# lower_pcb.net
KiCad netlist of a schematic drawn in EAGLE
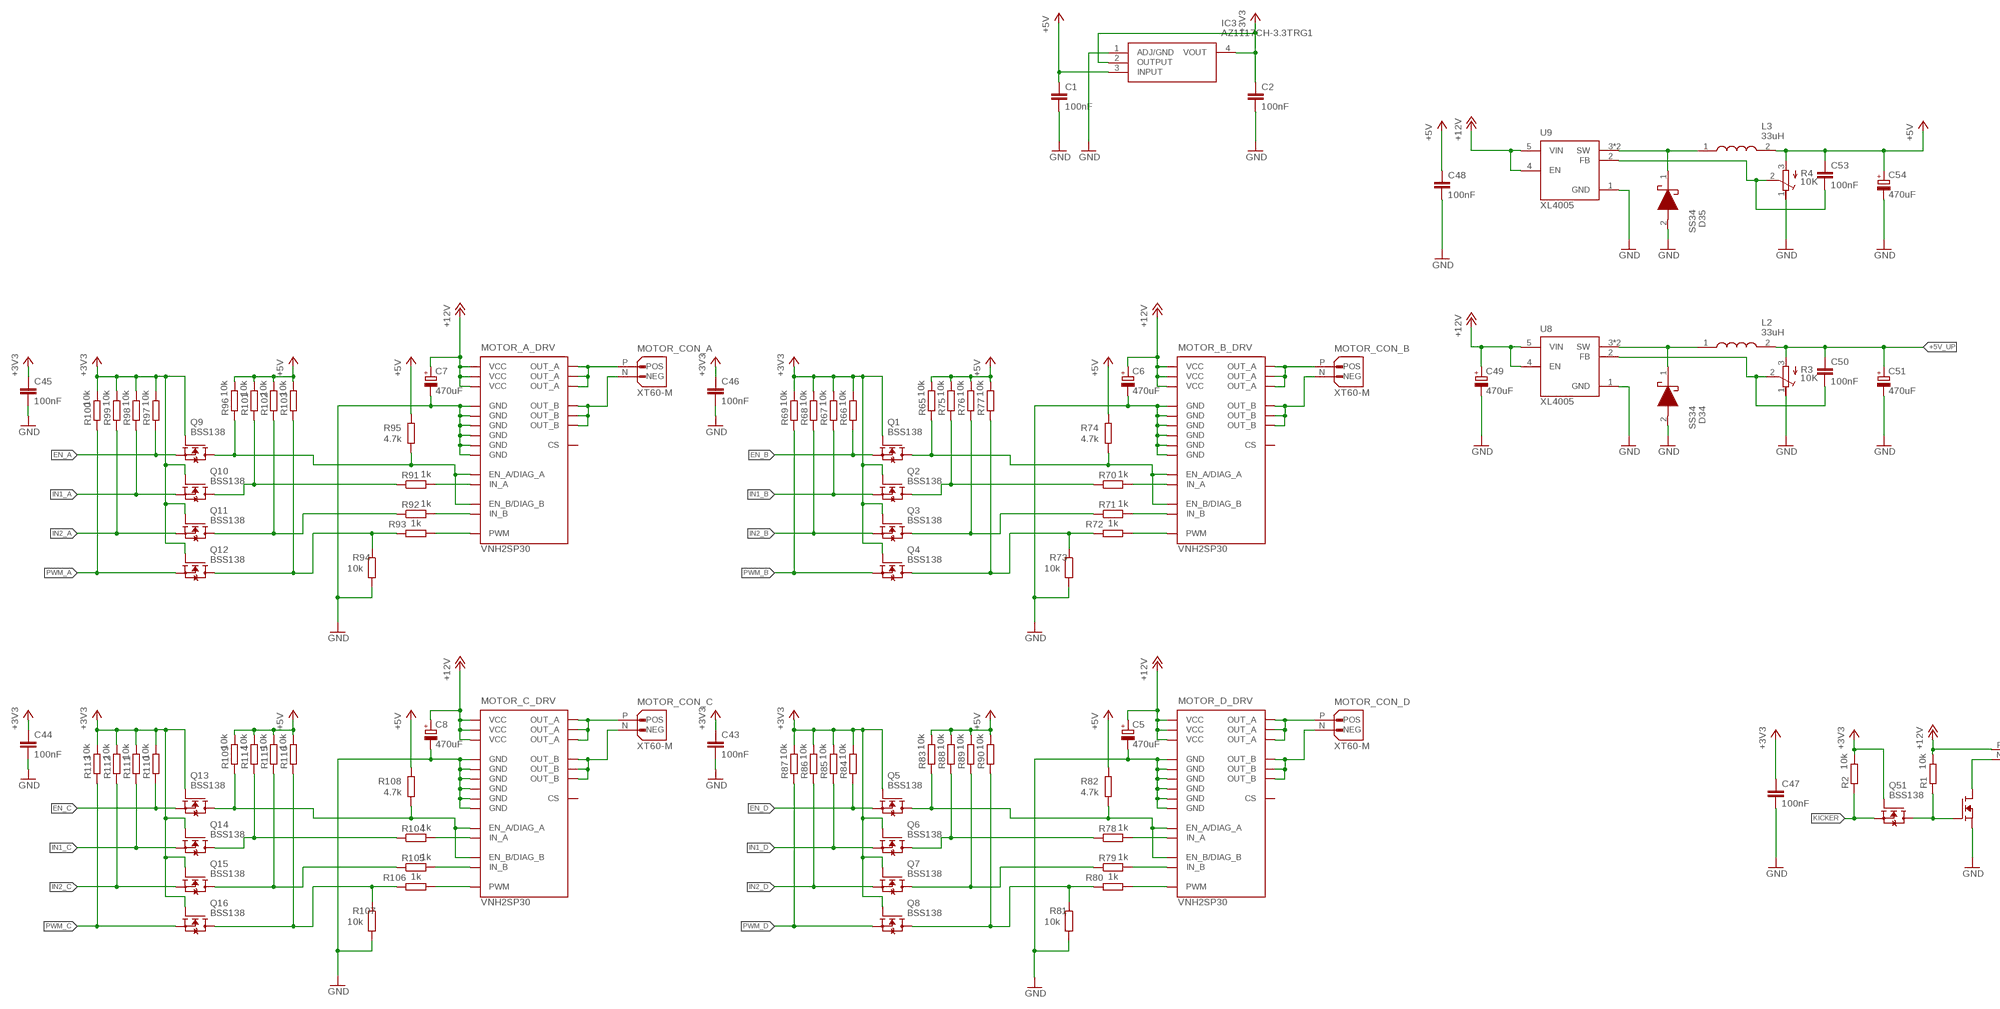
[diagram p0: schematic, sheet 1, part 1 of 2]
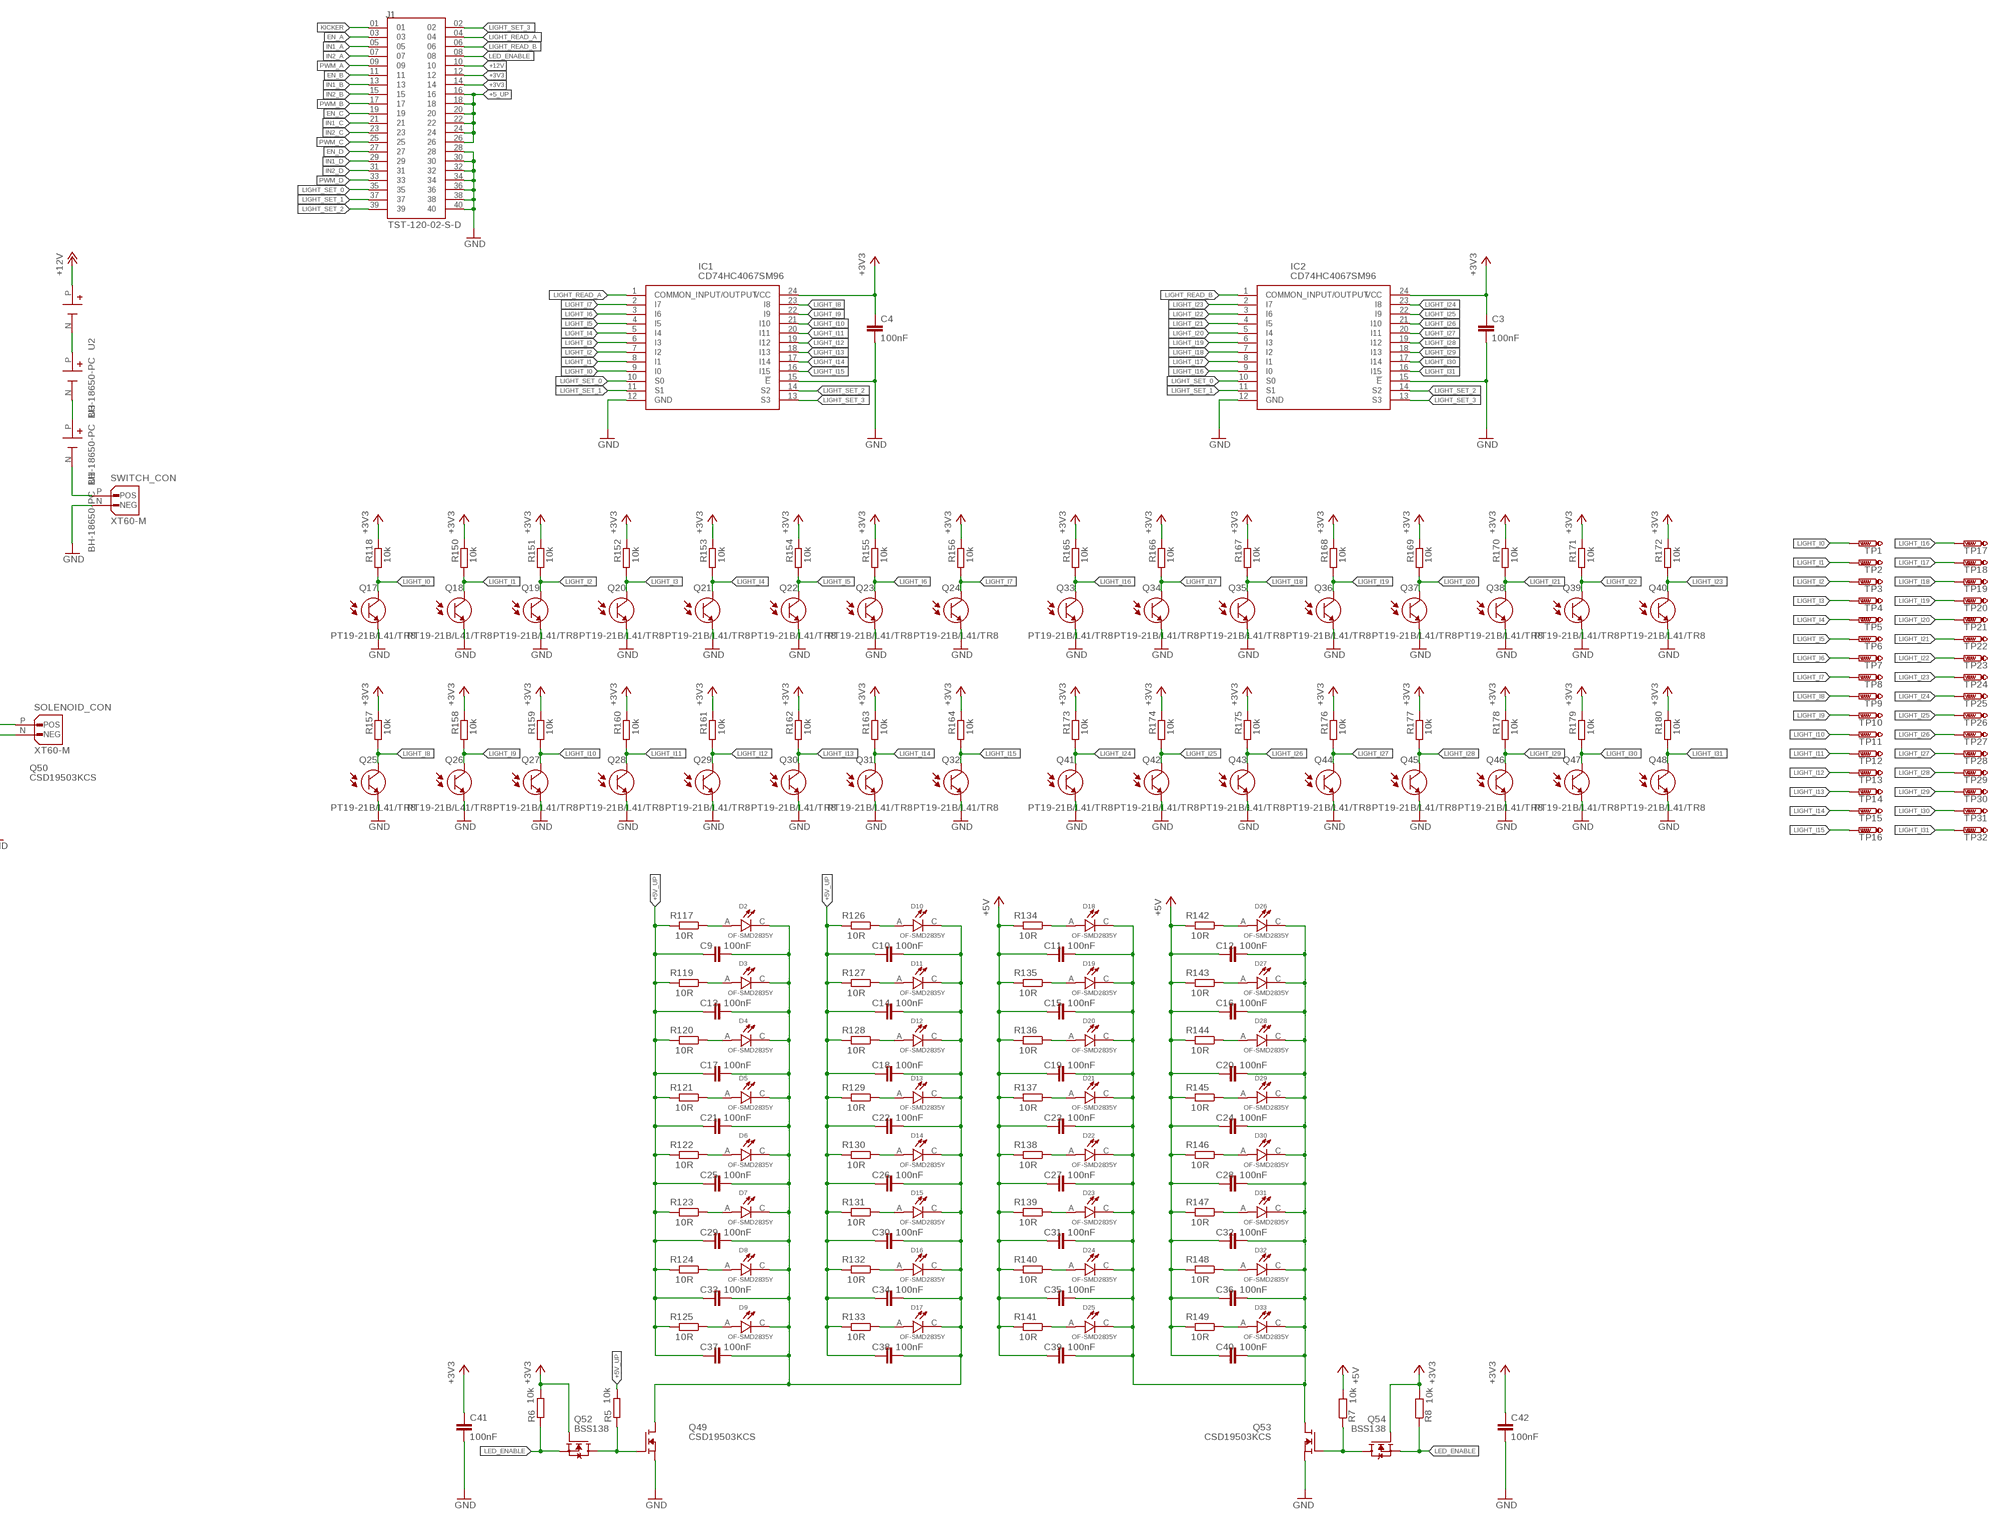
[diagram p1: schematic, sheet 1, part 2 of 2]

(export (version "E")
  (design (tool "Eeschema 10.0.6"))
  (components
    (comp (ref "C1")
      (value "100nF")
      (footprint "eagle-import:C0805")
      (libsource (lib "eagle-import") (part "C-EUC0805"))
    )
    (comp (ref "C2")
      (value "100nF")
      (footprint "eagle-import:C0805")
      (libsource (lib "eagle-import") (part "C-EUC0805"))
    )
    (comp (ref "C3")
      (value "100nF")
      (footprint "eagle-import:C0805")
      (libsource (lib "eagle-import") (part "C-EUC0805"))
    )
    (comp (ref "C4")
      (value "100nF")
      (footprint "eagle-import:C0805")
      (libsource (lib "eagle-import") (part "C-EUC0805"))
    )
    (comp (ref "C5")
      (value "470uF")
      (footprint "eagle-import:150CLZ-1010")
      (libsource (lib "eagle-import") (part "CPOL-EU150CLZ-1010"))
    )
    (comp (ref "C6")
      (value "470uF")
      (footprint "eagle-import:150CLZ-1010")
      (libsource (lib "eagle-import") (part "CPOL-EU150CLZ-1010"))
    )
    (comp (ref "C7")
      (value "470uF")
      (footprint "eagle-import:150CLZ-1010")
      (libsource (lib "eagle-import") (part "CPOL-EU150CLZ-1010"))
    )
    (comp (ref "C8")
      (value "470uF")
      (footprint "eagle-import:150CLZ-1010")
      (libsource (lib "eagle-import") (part "CPOL-EU150CLZ-1010"))
    )
    (comp (ref "C9")
      (value "100nF")
      (footprint "eagle-import:C0805")
      (libsource (lib "eagle-import") (part "C-EUC0805"))
    )
    (comp (ref "C10")
      (value "100nF")
      (footprint "eagle-import:C0805")
      (libsource (lib "eagle-import") (part "C-EUC0805"))
    )
    (comp (ref "C11")
      (value "100nF")
      (footprint "eagle-import:C0805")
      (libsource (lib "eagle-import") (part "C-EUC0805"))
    )
    (comp (ref "C12")
      (value "100nF")
      (footprint "eagle-import:C0805")
      (libsource (lib "eagle-import") (part "C-EUC0805"))
    )
    (comp (ref "C13")
      (value "100nF")
      (footprint "eagle-import:C0805")
      (libsource (lib "eagle-import") (part "C-EUC0805"))
    )
    (comp (ref "C14")
      (value "100nF")
      (footprint "eagle-import:C0805")
      (libsource (lib "eagle-import") (part "C-EUC0805"))
    )
    (comp (ref "C15")
      (value "100nF")
      (footprint "eagle-import:C0805")
      (libsource (lib "eagle-import") (part "C-EUC0805"))
    )
    (comp (ref "C16")
      (value "100nF")
      (footprint "eagle-import:C0805")
      (libsource (lib "eagle-import") (part "C-EUC0805"))
    )
    (comp (ref "C17")
      (value "100nF")
      (footprint "eagle-import:C0805")
      (libsource (lib "eagle-import") (part "C-EUC0805"))
    )
    (comp (ref "C18")
      (value "100nF")
      (footprint "eagle-import:C0805")
      (libsource (lib "eagle-import") (part "C-EUC0805"))
    )
    (comp (ref "C19")
      (value "100nF")
      (footprint "eagle-import:C0805")
      (libsource (lib "eagle-import") (part "C-EUC0805"))
    )
    (comp (ref "C20")
      (value "100nF")
      (footprint "eagle-import:C0805")
      (libsource (lib "eagle-import") (part "C-EUC0805"))
    )
    (comp (ref "C21")
      (value "100nF")
      (footprint "eagle-import:C0805")
      (libsource (lib "eagle-import") (part "C-EUC0805"))
    )
    (comp (ref "C22")
      (value "100nF")
      (footprint "eagle-import:C0805")
      (libsource (lib "eagle-import") (part "C-EUC0805"))
    )
    (comp (ref "C23")
      (value "100nF")
      (footprint "eagle-import:C0805")
      (libsource (lib "eagle-import") (part "C-EUC0805"))
    )
    (comp (ref "C24")
      (value "100nF")
      (footprint "eagle-import:C0805")
      (libsource (lib "eagle-import") (part "C-EUC0805"))
    )
    (comp (ref "C25")
      (value "100nF")
      (footprint "eagle-import:C0805")
      (libsource (lib "eagle-import") (part "C-EUC0805"))
    )
    (comp (ref "C26")
      (value "100nF")
      (footprint "eagle-import:C0805")
      (libsource (lib "eagle-import") (part "C-EUC0805"))
    )
    (comp (ref "C27")
      (value "100nF")
      (footprint "eagle-import:C0805")
      (libsource (lib "eagle-import") (part "C-EUC0805"))
    )
    (comp (ref "C28")
      (value "100nF")
      (footprint "eagle-import:C0805")
      (libsource (lib "eagle-import") (part "C-EUC0805"))
    )
    (comp (ref "C29")
      (value "100nF")
      (footprint "eagle-import:C0805")
      (libsource (lib "eagle-import") (part "C-EUC0805"))
    )
    (comp (ref "C30")
      (value "100nF")
      (footprint "eagle-import:C0805")
      (libsource (lib "eagle-import") (part "C-EUC0805"))
    )
    (comp (ref "C31")
      (value "100nF")
      (footprint "eagle-import:C0805")
      (libsource (lib "eagle-import") (part "C-EUC0805"))
    )
    (comp (ref "C32")
      (value "100nF")
      (footprint "eagle-import:C0805")
      (libsource (lib "eagle-import") (part "C-EUC0805"))
    )
    (comp (ref "C33")
      (value "100nF")
      (footprint "eagle-import:C0805")
      (libsource (lib "eagle-import") (part "C-EUC0805"))
    )
    (comp (ref "C34")
      (value "100nF")
      (footprint "eagle-import:C0805")
      (libsource (lib "eagle-import") (part "C-EUC0805"))
    )
    (comp (ref "C35")
      (value "100nF")
      (footprint "eagle-import:C0805")
      (libsource (lib "eagle-import") (part "C-EUC0805"))
    )
    (comp (ref "C36")
      (value "100nF")
      (footprint "eagle-import:C0805")
      (libsource (lib "eagle-import") (part "C-EUC0805"))
    )
    (comp (ref "C37")
      (value "100nF")
      (footprint "eagle-import:C0805")
      (libsource (lib "eagle-import") (part "C-EUC0805"))
    )
    (comp (ref "C38")
      (value "100nF")
      (footprint "eagle-import:C0805")
      (libsource (lib "eagle-import") (part "C-EUC0805"))
    )
    (comp (ref "C39")
      (value "100nF")
      (footprint "eagle-import:C0805")
      (libsource (lib "eagle-import") (part "C-EUC0805"))
    )
    (comp (ref "C40")
      (value "100nF")
      (footprint "eagle-import:C0805")
      (libsource (lib "eagle-import") (part "C-EUC0805"))
    )
    (comp (ref "C41")
      (value "100nF")
      (footprint "eagle-import:C0805")
      (libsource (lib "eagle-import") (part "C-EUC0805"))
    )
    (comp (ref "C42")
      (value "100nF")
      (footprint "eagle-import:C0805")
      (libsource (lib "eagle-import") (part "C-EUC0805"))
    )
    (comp (ref "C43")
      (value "100nF")
      (footprint "eagle-import:C0805")
      (libsource (lib "eagle-import") (part "C-EUC0805"))
    )
    (comp (ref "C44")
      (value "100nF")
      (footprint "eagle-import:C0805")
      (libsource (lib "eagle-import") (part "C-EUC0805"))
    )
    (comp (ref "C45")
      (value "100nF")
      (footprint "eagle-import:C0805")
      (libsource (lib "eagle-import") (part "C-EUC0805"))
    )
    (comp (ref "C46")
      (value "100nF")
      (footprint "eagle-import:C0805")
      (libsource (lib "eagle-import") (part "C-EUC0805"))
    )
    (comp (ref "C47")
      (value "100nF")
      (footprint "eagle-import:C0805")
      (libsource (lib "eagle-import") (part "C-EUC0805"))
    )
    (comp (ref "C48")
      (value "100nF")
      (footprint "eagle-import:C0805")
      (libsource (lib "eagle-import") (part "C-EUC0805"))
    )
    (comp (ref "C49")
      (value "470uF")
      (footprint "eagle-import:150CLZ-1010")
      (libsource (lib "eagle-import") (part "CPOL-EU150CLZ-1010"))
    )
    (comp (ref "C50")
      (value "100nF")
      (footprint "eagle-import:C0805")
      (libsource (lib "eagle-import") (part "C-EUC0805"))
    )
    (comp (ref "C51")
      (value "470uF")
      (footprint "eagle-import:150CLZ-1010")
      (libsource (lib "eagle-import") (part "CPOL-EU150CLZ-1010"))
    )
    (comp (ref "C53")
      (value "100nF")
      (footprint "eagle-import:C0805")
      (libsource (lib "eagle-import") (part "C-EUC0805"))
    )
    (comp (ref "C54")
      (value "470uF")
      (footprint "eagle-import:150CLZ-1010")
      (libsource (lib "eagle-import") (part "CPOL-EU150CLZ-1010"))
    )
    (comp (ref "D2")
      (value "OF-SMD2835Y")
      (footprint "eagle-import:LED_OF-SMD2835Y")
      (fields (field (name "MF") "Optoflash"))
      (libsource (lib "eagle-import") (part "OF-SMD2835Y"))
    )
    (comp (ref "D3")
      (value "OF-SMD2835Y")
      (footprint "eagle-import:LED_OF-SMD2835Y")
      (fields (field (name "MF") "Optoflash") (field (name "SPICEPREFIX") "D"))
      (libsource (lib "eagle-import") (part "OF-SMD2835Y"))
    )
    (comp (ref "D4")
      (value "OF-SMD2835Y")
      (footprint "eagle-import:LED_OF-SMD2835Y")
      (fields (field (name "MF") "Optoflash"))
      (libsource (lib "eagle-import") (part "OF-SMD2835Y"))
    )
    (comp (ref "D5")
      (value "OF-SMD2835Y")
      (footprint "eagle-import:LED_OF-SMD2835Y")
      (fields (field (name "MF") "Optoflash"))
      (libsource (lib "eagle-import") (part "OF-SMD2835Y"))
    )
    (comp (ref "D6")
      (value "OF-SMD2835Y")
      (footprint "eagle-import:LED_OF-SMD2835Y")
      (fields (field (name "MF") "Optoflash"))
      (libsource (lib "eagle-import") (part "OF-SMD2835Y"))
    )
    (comp (ref "D7")
      (value "OF-SMD2835Y")
      (footprint "eagle-import:LED_OF-SMD2835Y")
      (fields (field (name "MF") "Optoflash"))
      (libsource (lib "eagle-import") (part "OF-SMD2835Y"))
    )
    (comp (ref "D8")
      (value "OF-SMD2835Y")
      (footprint "eagle-import:LED_OF-SMD2835Y")
      (fields (field (name "MF") "Optoflash"))
      (libsource (lib "eagle-import") (part "OF-SMD2835Y"))
    )
    (comp (ref "D9")
      (value "OF-SMD2835Y")
      (footprint "eagle-import:LED_OF-SMD2835Y")
      (fields (field (name "MF") "Optoflash"))
      (libsource (lib "eagle-import") (part "OF-SMD2835Y"))
    )
    (comp (ref "D10")
      (value "OF-SMD2835Y")
      (footprint "eagle-import:LED_OF-SMD2835Y")
      (fields (field (name "MF") "Optoflash"))
      (libsource (lib "eagle-import") (part "OF-SMD2835Y"))
    )
    (comp (ref "D11")
      (value "OF-SMD2835Y")
      (footprint "eagle-import:LED_OF-SMD2835Y")
      (fields (field (name "MF") "Optoflash"))
      (libsource (lib "eagle-import") (part "OF-SMD2835Y"))
    )
    (comp (ref "D12")
      (value "OF-SMD2835Y")
      (footprint "eagle-import:LED_OF-SMD2835Y")
      (fields (field (name "MF") "Optoflash"))
      (libsource (lib "eagle-import") (part "OF-SMD2835Y"))
    )
    (comp (ref "D13")
      (value "OF-SMD2835Y")
      (footprint "eagle-import:LED_OF-SMD2835Y")
      (fields (field (name "MF") "Optoflash"))
      (libsource (lib "eagle-import") (part "OF-SMD2835Y"))
    )
    (comp (ref "D14")
      (value "OF-SMD2835Y")
      (footprint "eagle-import:LED_OF-SMD2835Y")
      (fields (field (name "MF") "Optoflash"))
      (libsource (lib "eagle-import") (part "OF-SMD2835Y"))
    )
    (comp (ref "D15")
      (value "OF-SMD2835Y")
      (footprint "eagle-import:LED_OF-SMD2835Y")
      (fields (field (name "MF") "Optoflash"))
      (libsource (lib "eagle-import") (part "OF-SMD2835Y"))
    )
    (comp (ref "D16")
      (value "OF-SMD2835Y")
      (footprint "eagle-import:LED_OF-SMD2835Y")
      (fields (field (name "MF") "Optoflash"))
      (libsource (lib "eagle-import") (part "OF-SMD2835Y"))
    )
    (comp (ref "D17")
      (value "OF-SMD2835Y")
      (footprint "eagle-import:LED_OF-SMD2835Y")
      (fields (field (name "MF") "Optoflash"))
      (libsource (lib "eagle-import") (part "OF-SMD2835Y"))
    )
    (comp (ref "D18")
      (value "OF-SMD2835Y")
      (footprint "eagle-import:LED_OF-SMD2835Y")
      (fields (field (name "MF") "Optoflash"))
      (libsource (lib "eagle-import") (part "OF-SMD2835Y"))
    )
    (comp (ref "D19")
      (value "OF-SMD2835Y")
      (footprint "eagle-import:LED_OF-SMD2835Y")
      (fields (field (name "MF") "Optoflash"))
      (libsource (lib "eagle-import") (part "OF-SMD2835Y"))
    )
    (comp (ref "D20")
      (value "OF-SMD2835Y")
      (footprint "eagle-import:LED_OF-SMD2835Y")
      (fields (field (name "MF") "Optoflash"))
      (libsource (lib "eagle-import") (part "OF-SMD2835Y"))
    )
    (comp (ref "D21")
      (value "OF-SMD2835Y")
      (footprint "eagle-import:LED_OF-SMD2835Y")
      (fields (field (name "MF") "Optoflash"))
      (libsource (lib "eagle-import") (part "OF-SMD2835Y"))
    )
    (comp (ref "D22")
      (value "OF-SMD2835Y")
      (footprint "eagle-import:LED_OF-SMD2835Y")
      (fields (field (name "MF") "Optoflash"))
      (libsource (lib "eagle-import") (part "OF-SMD2835Y"))
    )
    (comp (ref "D23")
      (value "OF-SMD2835Y")
      (footprint "eagle-import:LED_OF-SMD2835Y")
      (fields (field (name "MF") "Optoflash"))
      (libsource (lib "eagle-import") (part "OF-SMD2835Y"))
    )
    (comp (ref "D24")
      (value "OF-SMD2835Y")
      (footprint "eagle-import:LED_OF-SMD2835Y")
      (fields (field (name "MF") "Optoflash"))
      (libsource (lib "eagle-import") (part "OF-SMD2835Y"))
    )
    (comp (ref "D25")
      (value "OF-SMD2835Y")
      (footprint "eagle-import:LED_OF-SMD2835Y")
      (fields (field (name "MF") "Optoflash"))
      (libsource (lib "eagle-import") (part "OF-SMD2835Y"))
    )
    (comp (ref "D26")
      (value "OF-SMD2835Y")
      (footprint "eagle-import:LED_OF-SMD2835Y")
      (fields (field (name "MF") "Optoflash"))
      (libsource (lib "eagle-import") (part "OF-SMD2835Y"))
    )
    (comp (ref "D27")
      (value "OF-SMD2835Y")
      (footprint "eagle-import:LED_OF-SMD2835Y")
      (fields (field (name "MF") "Optoflash"))
      (libsource (lib "eagle-import") (part "OF-SMD2835Y"))
    )
    (comp (ref "D28")
      (value "OF-SMD2835Y")
      (footprint "eagle-import:LED_OF-SMD2835Y")
      (fields (field (name "MF") "Optoflash"))
      (libsource (lib "eagle-import") (part "OF-SMD2835Y"))
    )
    (comp (ref "D29")
      (value "OF-SMD2835Y")
      (footprint "eagle-import:LED_OF-SMD2835Y")
      (fields (field (name "MF") "Optoflash"))
      (libsource (lib "eagle-import") (part "OF-SMD2835Y"))
    )
    (comp (ref "D30")
      (value "OF-SMD2835Y")
      (footprint "eagle-import:LED_OF-SMD2835Y")
      (fields (field (name "MF") "Optoflash"))
      (libsource (lib "eagle-import") (part "OF-SMD2835Y"))
    )
    (comp (ref "D31")
      (value "OF-SMD2835Y")
      (footprint "eagle-import:LED_OF-SMD2835Y")
      (fields (field (name "MF") "Optoflash"))
      (libsource (lib "eagle-import") (part "OF-SMD2835Y"))
    )
    (comp (ref "D32")
      (value "OF-SMD2835Y")
      (footprint "eagle-import:LED_OF-SMD2835Y")
      (fields (field (name "MF") "Optoflash"))
      (libsource (lib "eagle-import") (part "OF-SMD2835Y"))
    )
    (comp (ref "D33")
      (value "OF-SMD2835Y")
      (footprint "eagle-import:LED_OF-SMD2835Y")
      (fields (field (name "MF") "Optoflash"))
      (libsource (lib "eagle-import") (part "OF-SMD2835Y"))
    )
    (comp (ref "D34")
      (value "SS34")
      (footprint "eagle-import:DIOM8059X256N")
      (fields (field (name "MOUSER_PART_NUMBER") "512-SS34"))
      (libsource (lib "eagle-import") (part "SS34"))
    )
    (comp (ref "D35")
      (value "SS34")
      (footprint "eagle-import:DIOM8059X256N")
      (fields (field (name "MOUSER_PART_NUMBER") "512-SS34"))
      (libsource (lib "eagle-import") (part "SS34"))
    )
    (comp (ref "IC1")
      (value "CD74HC4067SM96")
      (footprint "eagle-import:SOP65P780X200-24N")
      (fields (field (name "MOUSER_PART_NUMBER") "595-CD74HC4067SM96"))
      (libsource (lib "eagle-import") (part "CD74HC4067SM96"))
    )
    (comp (ref "IC2")
      (value "CD74HC4067SM96")
      (footprint "eagle-import:SOP65P780X200-24N")
      (fields (field (name "MOUSER_PART_NUMBER") "595-CD74HC4067SM96"))
      (libsource (lib "eagle-import") (part "CD74HC4067SM96"))
    )
    (comp (ref "IC3")
      (value "AZ1117CH-3.3TRG1")
      (footprint "eagle-import:SOT230P700X180-4N")
      (fields (field (name "MOUSER_PART_NUMBER") "621-AZ1117CH-3.3TRG1"))
      (libsource (lib "eagle-import") (part "AZ1117CH-3.3TRG1"))
    )
    (comp (ref "J1")
      (value "TST-120-02-S-D")
      (footprint "eagle-import:SAMTEC_TST-120-02-S-D")
      (fields (field (name "MF") "Samtec") (field (name "MP") "TST-120-02-S-D-20"))
      (libsource (lib "eagle-import") (part "TST-120-02-S-D"))
    )
    (comp (ref "L2")
      (value "33uH")
      (footprint "eagle-import:WE-HCI_1350_136523")
      (fields
        (field (name "MANUFACTURER_PART_NUMBER") "7443551151")
        (field (name "MOUSER_PART_NUMBER") "710-7443551151")
      )
      (libsource (lib "eagle-import") (part "7443551151"))
    )
    (comp (ref "L3")
      (value "33uH")
      (footprint "eagle-import:WE-HCI_1350_136523")
      (fields
        (field (name "MANUFACTURER_PART_NUMBER") "7443551151")
        (field (name "MOUSER_PART_NUMBER") "710-7443551151")
      )
      (libsource (lib "eagle-import") (part "7443551151"))
    )
    (comp (ref "MOTOR_A_DRV")
      (value "VNH2SP30")
      (footprint "eagle-import:MULTIPOWER30")
      (fields (field (name "MF") "STMicroelectronics") (field (name "SPICEPREFIX") "X"))
      (libsource (lib "eagle-import") (part "VNH2SP30"))
    )
    (comp (ref "MOTOR_B_DRV")
      (value "VNH2SP30")
      (footprint "eagle-import:MULTIPOWER30")
      (fields (field (name "MF") "STMicroelectronics") (field (name "SPICEPREFIX") "X"))
      (libsource (lib "eagle-import") (part "VNH2SP30"))
    )
    (comp (ref "MOTOR_CON_A")
      (value "XT60-M")
      (footprint "eagle-import:AMASS_XT60-M")
      (fields (field (name "MF") "AMASS"))
      (libsource (lib "eagle-import") (part "XT60-M"))
    )
    (comp (ref "MOTOR_CON_B")
      (value "XT60-M")
      (footprint "eagle-import:AMASS_XT60-M")
      (fields (field (name "MF") "AMASS"))
      (libsource (lib "eagle-import") (part "XT60-M"))
    )
    (comp (ref "MOTOR_CON_C")
      (value "XT60-M")
      (footprint "eagle-import:AMASS_XT60-M")
      (fields (field (name "MF") "AMASS"))
      (libsource (lib "eagle-import") (part "XT60-M"))
    )
    (comp (ref "MOTOR_CON_D")
      (value "XT60-M")
      (footprint "eagle-import:AMASS_XT60-M")
      (fields (field (name "MF") "AMASS"))
      (libsource (lib "eagle-import") (part "XT60-M"))
    )
    (comp (ref "MOTOR_C_DRV")
      (value "VNH2SP30")
      (footprint "eagle-import:MULTIPOWER30")
      (fields (field (name "MF") "STMicroelectronics") (field (name "SPICEPREFIX") "X"))
      (libsource (lib "eagle-import") (part "VNH2SP30"))
    )
    (comp (ref "MOTOR_D_DRV")
      (value "VNH2SP30")
      (footprint "eagle-import:MULTIPOWER30")
      (fields (field (name "MF") "STMicroelectronics") (field (name "SPICEPREFIX") "X"))
      (libsource (lib "eagle-import") (part "VNH2SP30"))
    )
    (comp (ref "Q1")
      (value "BSS138")
      (footprint "eagle-import:SOT95P240X111-3N")
      (fields (field (name "MF") "ON Semiconductor"))
      (libsource (lib "eagle-import") (part "BSS138"))
    )
    (comp (ref "Q2")
      (value "BSS138")
      (footprint "eagle-import:SOT95P240X111-3N")
      (fields (field (name "MF") "ON Semiconductor"))
      (libsource (lib "eagle-import") (part "BSS138"))
    )
    (comp (ref "Q3")
      (value "BSS138")
      (footprint "eagle-import:SOT95P240X111-3N")
      (fields (field (name "MF") "ON Semiconductor"))
      (libsource (lib "eagle-import") (part "BSS138"))
    )
    (comp (ref "Q4")
      (value "BSS138")
      (footprint "eagle-import:SOT95P240X111-3N")
      (fields (field (name "MF") "ON Semiconductor"))
      (libsource (lib "eagle-import") (part "BSS138"))
    )
    (comp (ref "Q5")
      (value "BSS138")
      (footprint "eagle-import:SOT95P240X111-3N")
      (fields (field (name "MF") "ON Semiconductor"))
      (libsource (lib "eagle-import") (part "BSS138"))
    )
    (comp (ref "Q6")
      (value "BSS138")
      (footprint "eagle-import:SOT95P240X111-3N")
      (fields (field (name "MF") "ON Semiconductor"))
      (libsource (lib "eagle-import") (part "BSS138"))
    )
    (comp (ref "Q7")
      (value "BSS138")
      (footprint "eagle-import:SOT95P240X111-3N")
      (fields (field (name "MF") "ON Semiconductor"))
      (libsource (lib "eagle-import") (part "BSS138"))
    )
    (comp (ref "Q8")
      (value "BSS138")
      (footprint "eagle-import:SOT95P240X111-3N")
      (fields (field (name "MF") "ON Semiconductor"))
      (libsource (lib "eagle-import") (part "BSS138"))
    )
    (comp (ref "Q9")
      (value "BSS138")
      (footprint "eagle-import:SOT95P240X111-3N")
      (fields (field (name "MF") "ON Semiconductor"))
      (libsource (lib "eagle-import") (part "BSS138"))
    )
    (comp (ref "Q10")
      (value "BSS138")
      (footprint "eagle-import:SOT95P240X111-3N")
      (fields (field (name "MF") "ON Semiconductor"))
      (libsource (lib "eagle-import") (part "BSS138"))
    )
    (comp (ref "Q11")
      (value "BSS138")
      (footprint "eagle-import:SOT95P240X111-3N")
      (fields (field (name "MF") "ON Semiconductor"))
      (libsource (lib "eagle-import") (part "BSS138"))
    )
    (comp (ref "Q12")
      (value "BSS138")
      (footprint "eagle-import:SOT95P240X111-3N")
      (fields (field (name "MF") "ON Semiconductor"))
      (libsource (lib "eagle-import") (part "BSS138"))
    )
    (comp (ref "Q13")
      (value "BSS138")
      (footprint "eagle-import:SOT95P240X111-3N")
      (fields (field (name "MF") "ON Semiconductor"))
      (libsource (lib "eagle-import") (part "BSS138"))
    )
    (comp (ref "Q14")
      (value "BSS138")
      (footprint "eagle-import:SOT95P240X111-3N")
      (fields (field (name "MF") "ON Semiconductor"))
      (libsource (lib "eagle-import") (part "BSS138"))
    )
    (comp (ref "Q15")
      (value "BSS138")
      (footprint "eagle-import:SOT95P240X111-3N")
      (fields (field (name "MF") "ON Semiconductor"))
      (libsource (lib "eagle-import") (part "BSS138"))
    )
    (comp (ref "Q16")
      (value "BSS138")
      (footprint "eagle-import:SOT95P240X111-3N")
      (fields (field (name "MF") "ON Semiconductor"))
      (libsource (lib "eagle-import") (part "BSS138"))
    )
    (comp (ref "Q17")
      (value "PT19-21B/L41/TR8")
      (footprint "eagle-import:XDCR_PT19-21B_L41_TR8")
      (fields (field (name "MF") "Everlight Electronics"))
      (libsource (lib "eagle-import") (part "PT19-21B/L41/TR8"))
    )
    (comp (ref "Q18")
      (value "PT19-21B/L41/TR8")
      (footprint "eagle-import:XDCR_PT19-21B_L41_TR8")
      (fields (field (name "MF") "Everlight Electronics"))
      (libsource (lib "eagle-import") (part "PT19-21B/L41/TR8"))
    )
    (comp (ref "Q19")
      (value "PT19-21B/L41/TR8")
      (footprint "eagle-import:XDCR_PT19-21B_L41_TR8")
      (fields (field (name "MF") "Everlight Electronics"))
      (libsource (lib "eagle-import") (part "PT19-21B/L41/TR8"))
    )
    (comp (ref "Q20")
      (value "PT19-21B/L41/TR8")
      (footprint "eagle-import:XDCR_PT19-21B_L41_TR8")
      (fields (field (name "MF") "Everlight Electronics"))
      (libsource (lib "eagle-import") (part "PT19-21B/L41/TR8"))
    )
    (comp (ref "Q21")
      (value "PT19-21B/L41/TR8")
      (footprint "eagle-import:XDCR_PT19-21B_L41_TR8")
      (fields (field (name "MF") "Everlight Electronics"))
      (libsource (lib "eagle-import") (part "PT19-21B/L41/TR8"))
    )
    (comp (ref "Q22")
      (value "PT19-21B/L41/TR8")
      (footprint "eagle-import:XDCR_PT19-21B_L41_TR8")
      (fields (field (name "MF") "Everlight Electronics"))
      (libsource (lib "eagle-import") (part "PT19-21B/L41/TR8"))
    )
    (comp (ref "Q23")
      (value "PT19-21B/L41/TR8")
      (footprint "eagle-import:XDCR_PT19-21B_L41_TR8")
      (fields (field (name "MF") "Everlight Electronics"))
      (libsource (lib "eagle-import") (part "PT19-21B/L41/TR8"))
    )
    (comp (ref "Q24")
      (value "PT19-21B/L41/TR8")
      (footprint "eagle-import:XDCR_PT19-21B_L41_TR8")
      (fields (field (name "MF") "Everlight Electronics"))
      (libsource (lib "eagle-import") (part "PT19-21B/L41/TR8"))
    )
    (comp (ref "Q25")
      (value "PT19-21B/L41/TR8")
      (footprint "eagle-import:XDCR_PT19-21B_L41_TR8")
      (fields (field (name "MF") "Everlight Electronics"))
      (libsource (lib "eagle-import") (part "PT19-21B/L41/TR8"))
    )
    (comp (ref "Q26")
      (value "PT19-21B/L41/TR8")
      (footprint "eagle-import:XDCR_PT19-21B_L41_TR8")
      (fields (field (name "MF") "Everlight Electronics"))
      (libsource (lib "eagle-import") (part "PT19-21B/L41/TR8"))
    )
    (comp (ref "Q27")
      (value "PT19-21B/L41/TR8")
      (footprint "eagle-import:XDCR_PT19-21B_L41_TR8")
      (fields (field (name "MF") "Everlight Electronics"))
      (libsource (lib "eagle-import") (part "PT19-21B/L41/TR8"))
    )
    (comp (ref "Q28")
      (value "PT19-21B/L41/TR8")
      (footprint "eagle-import:XDCR_PT19-21B_L41_TR8")
      (fields (field (name "MF") "Everlight Electronics"))
      (libsource (lib "eagle-import") (part "PT19-21B/L41/TR8"))
    )
    (comp (ref "Q29")
      (value "PT19-21B/L41/TR8")
      (footprint "eagle-import:XDCR_PT19-21B_L41_TR8")
      (fields (field (name "MF") "Everlight Electronics"))
      (libsource (lib "eagle-import") (part "PT19-21B/L41/TR8"))
    )
    (comp (ref "Q30")
      (value "PT19-21B/L41/TR8")
      (footprint "eagle-import:XDCR_PT19-21B_L41_TR8")
      (fields (field (name "MF") "Everlight Electronics"))
      (libsource (lib "eagle-import") (part "PT19-21B/L41/TR8"))
    )
    (comp (ref "Q31")
      (value "PT19-21B/L41/TR8")
      (footprint "eagle-import:XDCR_PT19-21B_L41_TR8")
      (fields (field (name "MF") "Everlight Electronics"))
      (libsource (lib "eagle-import") (part "PT19-21B/L41/TR8"))
    )
    (comp (ref "Q32")
      (value "PT19-21B/L41/TR8")
      (footprint "eagle-import:XDCR_PT19-21B_L41_TR8")
      (fields (field (name "MF") "Everlight Electronics"))
      (libsource (lib "eagle-import") (part "PT19-21B/L41/TR8"))
    )
    (comp (ref "Q33")
      (value "PT19-21B/L41/TR8")
      (footprint "eagle-import:XDCR_PT19-21B_L41_TR8")
      (fields (field (name "MF") "Everlight Electronics"))
      (libsource (lib "eagle-import") (part "PT19-21B/L41/TR8"))
    )
    (comp (ref "Q34")
      (value "PT19-21B/L41/TR8")
      (footprint "eagle-import:XDCR_PT19-21B_L41_TR8")
      (fields (field (name "MF") "Everlight Electronics"))
      (libsource (lib "eagle-import") (part "PT19-21B/L41/TR8"))
    )
    (comp (ref "Q35")
      (value "PT19-21B/L41/TR8")
      (footprint "eagle-import:XDCR_PT19-21B_L41_TR8")
      (fields (field (name "MF") "Everlight Electronics"))
      (libsource (lib "eagle-import") (part "PT19-21B/L41/TR8"))
    )
    (comp (ref "Q36")
      (value "PT19-21B/L41/TR8")
      (footprint "eagle-import:XDCR_PT19-21B_L41_TR8")
      (fields (field (name "MF") "Everlight Electronics"))
      (libsource (lib "eagle-import") (part "PT19-21B/L41/TR8"))
    )
    (comp (ref "Q37")
      (value "PT19-21B/L41/TR8")
      (footprint "eagle-import:XDCR_PT19-21B_L41_TR8")
      (fields (field (name "MF") "Everlight Electronics"))
      (libsource (lib "eagle-import") (part "PT19-21B/L41/TR8"))
    )
    (comp (ref "Q38")
      (value "PT19-21B/L41/TR8")
      (footprint "eagle-import:XDCR_PT19-21B_L41_TR8")
      (fields (field (name "MF") "Everlight Electronics"))
      (libsource (lib "eagle-import") (part "PT19-21B/L41/TR8"))
    )
    (comp (ref "Q39")
      (value "PT19-21B/L41/TR8")
      (footprint "eagle-import:XDCR_PT19-21B_L41_TR8")
      (fields (field (name "MF") "Everlight Electronics"))
      (libsource (lib "eagle-import") (part "PT19-21B/L41/TR8"))
    )
    (comp (ref "Q40")
      (value "PT19-21B/L41/TR8")
      (footprint "eagle-import:XDCR_PT19-21B_L41_TR8")
      (fields (field (name "MF") "Everlight Electronics"))
      (libsource (lib "eagle-import") (part "PT19-21B/L41/TR8"))
    )
    (comp (ref "Q41")
      (value "PT19-21B/L41/TR8")
      (footprint "eagle-import:XDCR_PT19-21B_L41_TR8")
      (fields (field (name "MF") "Everlight Electronics"))
      (libsource (lib "eagle-import") (part "PT19-21B/L41/TR8"))
    )
    (comp (ref "Q42")
      (value "PT19-21B/L41/TR8")
      (footprint "eagle-import:XDCR_PT19-21B_L41_TR8")
      (fields (field (name "MF") "Everlight Electronics"))
      (libsource (lib "eagle-import") (part "PT19-21B/L41/TR8"))
    )
    (comp (ref "Q43")
      (value "PT19-21B/L41/TR8")
      (footprint "eagle-import:XDCR_PT19-21B_L41_TR8")
      (fields (field (name "MF") "Everlight Electronics"))
      (libsource (lib "eagle-import") (part "PT19-21B/L41/TR8"))
    )
    (comp (ref "Q44")
      (value "PT19-21B/L41/TR8")
      (footprint "eagle-import:XDCR_PT19-21B_L41_TR8")
      (fields (field (name "MF") "Everlight Electronics"))
      (libsource (lib "eagle-import") (part "PT19-21B/L41/TR8"))
    )
    (comp (ref "Q45")
      (value "PT19-21B/L41/TR8")
      (footprint "eagle-import:XDCR_PT19-21B_L41_TR8")
      (fields (field (name "MF") "Everlight Electronics"))
      (libsource (lib "eagle-import") (part "PT19-21B/L41/TR8"))
    )
    (comp (ref "Q46")
      (value "PT19-21B/L41/TR8")
      (footprint "eagle-import:XDCR_PT19-21B_L41_TR8")
      (fields (field (name "MF") "Everlight Electronics"))
      (libsource (lib "eagle-import") (part "PT19-21B/L41/TR8"))
    )
    (comp (ref "Q47")
      (value "PT19-21B/L41/TR8")
      (footprint "eagle-import:XDCR_PT19-21B_L41_TR8")
      (fields (field (name "MF") "Everlight Electronics"))
      (libsource (lib "eagle-import") (part "PT19-21B/L41/TR8"))
    )
    (comp (ref "Q48")
      (value "PT19-21B/L41/TR8")
      (footprint "eagle-import:XDCR_PT19-21B_L41_TR8")
      (fields (field (name "MF") "Everlight Electronics"))
      (libsource (lib "eagle-import") (part "PT19-21B/L41/TR8"))
    )
    (comp (ref "Q49")
      (value "CSD19503KCS")
      (footprint "eagle-import:TO254P1036X470X1965-3")
      (fields (field (name "MF") "Texas Instruments"))
      (libsource (lib "eagle-import") (part "CSD19503KCS"))
    )
    (comp (ref "Q50")
      (value "CSD19503KCS")
      (footprint "eagle-import:TO254P1036X470X1965-3")
      (fields (field (name "MF") "Texas Instruments"))
      (libsource (lib "eagle-import") (part "CSD19503KCS"))
    )
    (comp (ref "Q51")
      (value "BSS138")
      (footprint "eagle-import:SOT95P240X111-3N")
      (fields (field (name "MF") "ON Semiconductor"))
      (libsource (lib "eagle-import") (part "BSS138"))
    )
    (comp (ref "Q52")
      (value "BSS138")
      (footprint "eagle-import:SOT95P240X111-3N")
      (fields (field (name "MF") "ON Semiconductor"))
      (libsource (lib "eagle-import") (part "BSS138"))
    )
    (comp (ref "Q53")
      (value "CSD19503KCS")
      (footprint "eagle-import:TO254P1036X470X1965-3")
      (fields (field (name "MF") "Texas Instruments"))
      (libsource (lib "eagle-import") (part "CSD19503KCS"))
    )
    (comp (ref "Q54")
      (value "BSS138")
      (footprint "eagle-import:SOT95P240X111-3N")
      (fields (field (name "MF") "ON Semiconductor"))
      (libsource (lib "eagle-import") (part "BSS138"))
    )
    (comp (ref "R1")
      (value "10k")
      (footprint "eagle-import:R1206")
      (libsource (lib "eagle-import") (part "R-EU_R1206"))
    )
    (comp (ref "R2")
      (value "10k")
      (footprint "eagle-import:R1206")
      (libsource (lib "eagle-import") (part "R-EU_R1206"))
    )
    (comp (ref "R3")
      (value "10K")
      (footprint "eagle-import:RTRIM3314J")
      (libsource (lib "eagle-import") (part "R-TRIMM3314J"))
    )
    (comp (ref "R4")
      (value "10K")
      (footprint "eagle-import:RTRIM3314J")
      (libsource (lib "eagle-import") (part "R-TRIMM3314J"))
    )
    (comp (ref "R5")
      (value "10k")
      (footprint "eagle-import:R1206")
      (libsource (lib "eagle-import") (part "R-EU_R1206"))
    )
    (comp (ref "R6")
      (value "10k")
      (footprint "eagle-import:R1206")
      (libsource (lib "eagle-import") (part "R-EU_R1206"))
    )
    (comp (ref "R7")
      (value "10k")
      (footprint "eagle-import:R1206")
      (libsource (lib "eagle-import") (part "R-EU_R1206"))
    )
    (comp (ref "R8")
      (value "10k")
      (footprint "eagle-import:R1206")
      (libsource (lib "eagle-import") (part "R-EU_R1206"))
    )
    (comp (ref "R65")
      (value "10k")
      (footprint "eagle-import:R1206")
      (libsource (lib "eagle-import") (part "R-EU_R1206"))
    )
    (comp (ref "R66")
      (value "10k")
      (footprint "eagle-import:R1206")
      (libsource (lib "eagle-import") (part "R-EU_R1206"))
    )
    (comp (ref "R67")
      (value "10k")
      (footprint "eagle-import:R1206")
      (libsource (lib "eagle-import") (part "R-EU_R1206"))
    )
    (comp (ref "R68")
      (value "10k")
      (footprint "eagle-import:R1206")
      (libsource (lib "eagle-import") (part "R-EU_R1206"))
    )
    (comp (ref "R69")
      (value "10k")
      (footprint "eagle-import:R1206")
      (libsource (lib "eagle-import") (part "R-EU_R1206"))
    )
    (comp (ref "R70")
      (value "1k")
      (footprint "eagle-import:R1206")
      (libsource (lib "eagle-import") (part "R-EU_R1206"))
    )
    (comp (ref "R71")
      (value "1k")
      (footprint "eagle-import:R1206")
      (libsource (lib "eagle-import") (part "R-EU_R1206"))
    )
    (comp (ref "R72")
      (value "1k")
      (footprint "eagle-import:R1206")
      (libsource (lib "eagle-import") (part "R-EU_R1206"))
    )
    (comp (ref "R73")
      (value "10k")
      (footprint "eagle-import:R1206")
      (libsource (lib "eagle-import") (part "R-EU_R1206"))
    )
    (comp (ref "R74")
      (value "4.7k")
      (footprint "eagle-import:R1206")
      (libsource (lib "eagle-import") (part "R-EU_R1206"))
    )
    (comp (ref "R75")
      (value "10k")
      (footprint "eagle-import:R1206")
      (libsource (lib "eagle-import") (part "R-EU_R1206"))
    )
    (comp (ref "R76")
      (value "10k")
      (footprint "eagle-import:R1206")
      (libsource (lib "eagle-import") (part "R-EU_R1206"))
    )
    (comp (ref "R77")
      (value "10k")
      (footprint "eagle-import:R1206")
      (libsource (lib "eagle-import") (part "R-EU_R1206"))
    )
    (comp (ref "R78")
      (value "1k")
      (footprint "eagle-import:R1206")
      (libsource (lib "eagle-import") (part "R-EU_R1206"))
    )
    (comp (ref "R79")
      (value "1k")
      (footprint "eagle-import:R1206")
      (libsource (lib "eagle-import") (part "R-EU_R1206"))
    )
    (comp (ref "R80")
      (value "1k")
      (footprint "eagle-import:R1206")
      (libsource (lib "eagle-import") (part "R-EU_R1206"))
    )
    (comp (ref "R81")
      (value "10k")
      (footprint "eagle-import:R1206")
      (libsource (lib "eagle-import") (part "R-EU_R1206"))
    )
    (comp (ref "R82")
      (value "4.7k")
      (footprint "eagle-import:R1206")
      (libsource (lib "eagle-import") (part "R-EU_R1206"))
    )
    (comp (ref "R83")
      (value "10k")
      (footprint "eagle-import:R1206")
      (libsource (lib "eagle-import") (part "R-EU_R1206"))
    )
    (comp (ref "R84")
      (value "10k")
      (footprint "eagle-import:R1206")
      (libsource (lib "eagle-import") (part "R-EU_R1206"))
    )
    (comp (ref "R85")
      (value "10k")
      (footprint "eagle-import:R1206")
      (libsource (lib "eagle-import") (part "R-EU_R1206"))
    )
    (comp (ref "R86")
      (value "10k")
      (footprint "eagle-import:R1206")
      (libsource (lib "eagle-import") (part "R-EU_R1206"))
    )
    (comp (ref "R87")
      (value "10k")
      (footprint "eagle-import:R1206")
      (libsource (lib "eagle-import") (part "R-EU_R1206"))
    )
    (comp (ref "R88")
      (value "10k")
      (footprint "eagle-import:R1206")
      (libsource (lib "eagle-import") (part "R-EU_R1206"))
    )
    (comp (ref "R89")
      (value "10k")
      (footprint "eagle-import:R1206")
      (libsource (lib "eagle-import") (part "R-EU_R1206"))
    )
    (comp (ref "R90")
      (value "10k")
      (footprint "eagle-import:R1206")
      (libsource (lib "eagle-import") (part "R-EU_R1206"))
    )
    (comp (ref "R91")
      (value "1k")
      (footprint "eagle-import:R1206")
      (libsource (lib "eagle-import") (part "R-EU_R1206"))
    )
    (comp (ref "R92")
      (value "1k")
      (footprint "eagle-import:R1206")
      (libsource (lib "eagle-import") (part "R-EU_R1206"))
    )
    (comp (ref "R93")
      (value "1k")
      (footprint "eagle-import:R1206")
      (libsource (lib "eagle-import") (part "R-EU_R1206"))
    )
    (comp (ref "R94")
      (value "10k")
      (footprint "eagle-import:R1206")
      (libsource (lib "eagle-import") (part "R-EU_R1206"))
    )
    (comp (ref "R95")
      (value "4.7k")
      (footprint "eagle-import:R1206")
      (libsource (lib "eagle-import") (part "R-EU_R1206"))
    )
    (comp (ref "R96")
      (value "10k")
      (footprint "eagle-import:R1206")
      (libsource (lib "eagle-import") (part "R-EU_R1206"))
    )
    (comp (ref "R97")
      (value "10k")
      (footprint "eagle-import:R1206")
      (libsource (lib "eagle-import") (part "R-EU_R1206"))
    )
    (comp (ref "R98")
      (value "10k")
      (footprint "eagle-import:R1206")
      (libsource (lib "eagle-import") (part "R-EU_R1206"))
    )
    (comp (ref "R99")
      (value "10k")
      (footprint "eagle-import:R1206")
      (libsource (lib "eagle-import") (part "R-EU_R1206"))
    )
    (comp (ref "R100")
      (value "10k")
      (footprint "eagle-import:R1206")
      (libsource (lib "eagle-import") (part "R-EU_R1206"))
    )
    (comp (ref "R101")
      (value "10k")
      (footprint "eagle-import:R1206")
      (libsource (lib "eagle-import") (part "R-EU_R1206"))
    )
    (comp (ref "R102")
      (value "10k")
      (footprint "eagle-import:R1206")
      (libsource (lib "eagle-import") (part "R-EU_R1206"))
    )
    (comp (ref "R103")
      (value "10k")
      (footprint "eagle-import:R1206")
      (libsource (lib "eagle-import") (part "R-EU_R1206"))
    )
    (comp (ref "R104")
      (value "1k")
      (footprint "eagle-import:R1206")
      (libsource (lib "eagle-import") (part "R-EU_R1206"))
    )
    (comp (ref "R105")
      (value "1k")
      (footprint "eagle-import:R1206")
      (libsource (lib "eagle-import") (part "R-EU_R1206"))
    )
    (comp (ref "R106")
      (value "1k")
      (footprint "eagle-import:R1206")
      (libsource (lib "eagle-import") (part "R-EU_R1206"))
    )
    (comp (ref "R107")
      (value "10k")
      (footprint "eagle-import:R1206")
      (libsource (lib "eagle-import") (part "R-EU_R1206"))
    )
    (comp (ref "R108")
      (value "4.7k")
      (footprint "eagle-import:R1206")
      (libsource (lib "eagle-import") (part "R-EU_R1206"))
    )
    (comp (ref "R109")
      (value "10k")
      (footprint "eagle-import:R1206")
      (libsource (lib "eagle-import") (part "R-EU_R1206"))
    )
    (comp (ref "R110")
      (value "10k")
      (footprint "eagle-import:R1206")
      (libsource (lib "eagle-import") (part "R-EU_R1206"))
    )
    (comp (ref "R111")
      (value "10k")
      (footprint "eagle-import:R1206")
      (libsource (lib "eagle-import") (part "R-EU_R1206"))
    )
    (comp (ref "R112")
      (value "10k")
      (footprint "eagle-import:R1206")
      (libsource (lib "eagle-import") (part "R-EU_R1206"))
    )
    (comp (ref "R113")
      (value "10k")
      (footprint "eagle-import:R1206")
      (libsource (lib "eagle-import") (part "R-EU_R1206"))
    )
    (comp (ref "R114")
      (value "10k")
      (footprint "eagle-import:R1206")
      (libsource (lib "eagle-import") (part "R-EU_R1206"))
    )
    (comp (ref "R115")
      (value "10k")
      (footprint "eagle-import:R1206")
      (libsource (lib "eagle-import") (part "R-EU_R1206"))
    )
    (comp (ref "R116")
      (value "10k")
      (footprint "eagle-import:R1206")
      (libsource (lib "eagle-import") (part "R-EU_R1206"))
    )
    (comp (ref "R117")
      (value "10R")
      (footprint "eagle-import:R1206")
      (libsource (lib "eagle-import") (part "R-EU_R1206"))
    )
    (comp (ref "R118")
      (value "10k")
      (footprint "eagle-import:R1206")
      (libsource (lib "eagle-import") (part "R-EU_R1206"))
    )
    (comp (ref "R119")
      (value "10R")
      (footprint "eagle-import:R1206")
      (libsource (lib "eagle-import") (part "R-EU_R1206"))
    )
    (comp (ref "R120")
      (value "10R")
      (footprint "eagle-import:R1206")
      (libsource (lib "eagle-import") (part "R-EU_R1206"))
    )
    (comp (ref "R121")
      (value "10R")
      (footprint "eagle-import:R1206")
      (libsource (lib "eagle-import") (part "R-EU_R1206"))
    )
    (comp (ref "R122")
      (value "10R")
      (footprint "eagle-import:R1206")
      (libsource (lib "eagle-import") (part "R-EU_R1206"))
    )
    (comp (ref "R123")
      (value "10R")
      (footprint "eagle-import:R1206")
      (libsource (lib "eagle-import") (part "R-EU_R1206"))
    )
    (comp (ref "R124")
      (value "10R")
      (footprint "eagle-import:R1206")
      (libsource (lib "eagle-import") (part "R-EU_R1206"))
    )
    (comp (ref "R125")
      (value "10R")
      (footprint "eagle-import:R1206")
      (libsource (lib "eagle-import") (part "R-EU_R1206"))
    )
    (comp (ref "R126")
      (value "10R")
      (footprint "eagle-import:R1206")
      (libsource (lib "eagle-import") (part "R-EU_R1206"))
    )
    (comp (ref "R127")
      (value "10R")
      (footprint "eagle-import:R1206")
      (libsource (lib "eagle-import") (part "R-EU_R1206"))
    )
    (comp (ref "R128")
      (value "10R")
      (footprint "eagle-import:R1206")
      (libsource (lib "eagle-import") (part "R-EU_R1206"))
    )
    (comp (ref "R129")
      (value "10R")
      (footprint "eagle-import:R1206")
      (libsource (lib "eagle-import") (part "R-EU_R1206"))
    )
    (comp (ref "R130")
      (value "10R")
      (footprint "eagle-import:R1206")
      (libsource (lib "eagle-import") (part "R-EU_R1206"))
    )
    (comp (ref "R131")
      (value "10R")
      (footprint "eagle-import:R1206")
      (libsource (lib "eagle-import") (part "R-EU_R1206"))
    )
    (comp (ref "R132")
      (value "10R")
      (footprint "eagle-import:R1206")
      (libsource (lib "eagle-import") (part "R-EU_R1206"))
    )
    (comp (ref "R133")
      (value "10R")
      (footprint "eagle-import:R1206")
      (libsource (lib "eagle-import") (part "R-EU_R1206"))
    )
    (comp (ref "R134")
      (value "10R")
      (footprint "eagle-import:R1206")
      (libsource (lib "eagle-import") (part "R-EU_R1206"))
    )
    (comp (ref "R135")
      (value "10R")
      (footprint "eagle-import:R1206")
      (libsource (lib "eagle-import") (part "R-EU_R1206"))
    )
    (comp (ref "R136")
      (value "10R")
      (footprint "eagle-import:R1206")
      (libsource (lib "eagle-import") (part "R-EU_R1206"))
    )
    (comp (ref "R137")
      (value "10R")
      (footprint "eagle-import:R1206")
      (libsource (lib "eagle-import") (part "R-EU_R1206"))
    )
    (comp (ref "R138")
      (value "10R")
      (footprint "eagle-import:R1206")
      (libsource (lib "eagle-import") (part "R-EU_R1206"))
    )
    (comp (ref "R139")
      (value "10R")
      (footprint "eagle-import:R1206")
      (libsource (lib "eagle-import") (part "R-EU_R1206"))
    )
    (comp (ref "R140")
      (value "10R")
      (footprint "eagle-import:R1206")
      (libsource (lib "eagle-import") (part "R-EU_R1206"))
    )
    (comp (ref "R141")
      (value "10R")
      (footprint "eagle-import:R1206")
      (libsource (lib "eagle-import") (part "R-EU_R1206"))
    )
    (comp (ref "R142")
      (value "10R")
      (footprint "eagle-import:R1206")
      (libsource (lib "eagle-import") (part "R-EU_R1206"))
    )
    (comp (ref "R143")
      (value "10R")
      (footprint "eagle-import:R1206")
      (libsource (lib "eagle-import") (part "R-EU_R1206"))
    )
    (comp (ref "R144")
      (value "10R")
      (footprint "eagle-import:R1206")
      (libsource (lib "eagle-import") (part "R-EU_R1206"))
    )
    (comp (ref "R145")
      (value "10R")
      (footprint "eagle-import:R1206")
      (libsource (lib "eagle-import") (part "R-EU_R1206"))
    )
    (comp (ref "R146")
      (value "10R")
      (footprint "eagle-import:R1206")
      (libsource (lib "eagle-import") (part "R-EU_R1206"))
    )
    (comp (ref "R147")
      (value "10R")
      (footprint "eagle-import:R1206")
      (libsource (lib "eagle-import") (part "R-EU_R1206"))
    )
    (comp (ref "R148")
      (value "10R")
      (footprint "eagle-import:R1206")
      (libsource (lib "eagle-import") (part "R-EU_R1206"))
    )
    (comp (ref "R149")
      (value "10R")
      (footprint "eagle-import:R1206")
      (libsource (lib "eagle-import") (part "R-EU_R1206"))
    )
    (comp (ref "R150")
      (value "10k")
      (footprint "eagle-import:R1206")
      (libsource (lib "eagle-import") (part "R-EU_R1206"))
    )
    (comp (ref "R151")
      (value "10k")
      (footprint "eagle-import:R1206")
      (libsource (lib "eagle-import") (part "R-EU_R1206"))
    )
    (comp (ref "R152")
      (value "10k")
      (footprint "eagle-import:R1206")
      (libsource (lib "eagle-import") (part "R-EU_R1206"))
    )
    (comp (ref "R153")
      (value "10k")
      (footprint "eagle-import:R1206")
      (libsource (lib "eagle-import") (part "R-EU_R1206"))
    )
    (comp (ref "R154")
      (value "10k")
      (footprint "eagle-import:R1206")
      (libsource (lib "eagle-import") (part "R-EU_R1206"))
    )
    (comp (ref "R155")
      (value "10k")
      (footprint "eagle-import:R1206")
      (libsource (lib "eagle-import") (part "R-EU_R1206"))
    )
    (comp (ref "R156")
      (value "10k")
      (footprint "eagle-import:R1206")
      (libsource (lib "eagle-import") (part "R-EU_R1206"))
    )
    (comp (ref "R157")
      (value "10k")
      (footprint "eagle-import:R1206")
      (libsource (lib "eagle-import") (part "R-EU_R1206"))
    )
    (comp (ref "R158")
      (value "10k")
      (footprint "eagle-import:R1206")
      (libsource (lib "eagle-import") (part "R-EU_R1206"))
    )
    (comp (ref "R159")
      (value "10k")
      (footprint "eagle-import:R1206")
      (libsource (lib "eagle-import") (part "R-EU_R1206"))
    )
    (comp (ref "R160")
      (value "10k")
      (footprint "eagle-import:R1206")
      (libsource (lib "eagle-import") (part "R-EU_R1206"))
    )
    (comp (ref "R161")
      (value "10k")
      (footprint "eagle-import:R1206")
      (libsource (lib "eagle-import") (part "R-EU_R1206"))
    )
    (comp (ref "R162")
      (value "10k")
      (footprint "eagle-import:R1206")
      (libsource (lib "eagle-import") (part "R-EU_R1206"))
    )
    (comp (ref "R163")
      (value "10k")
      (footprint "eagle-import:R1206")
      (libsource (lib "eagle-import") (part "R-EU_R1206"))
    )
    (comp (ref "R164")
      (value "10k")
      (footprint "eagle-import:R1206")
      (libsource (lib "eagle-import") (part "R-EU_R1206"))
    )
    (comp (ref "R165")
      (value "10k")
      (footprint "eagle-import:R1206")
      (libsource (lib "eagle-import") (part "R-EU_R1206"))
    )
    (comp (ref "R166")
      (value "10k")
      (footprint "eagle-import:R1206")
      (libsource (lib "eagle-import") (part "R-EU_R1206"))
    )
    (comp (ref "R167")
      (value "10k")
      (footprint "eagle-import:R1206")
      (libsource (lib "eagle-import") (part "R-EU_R1206"))
    )
    (comp (ref "R168")
      (value "10k")
      (footprint "eagle-import:R1206")
      (libsource (lib "eagle-import") (part "R-EU_R1206"))
    )
    (comp (ref "R169")
      (value "10k")
      (footprint "eagle-import:R1206")
      (libsource (lib "eagle-import") (part "R-EU_R1206"))
    )
    (comp (ref "R170")
      (value "10k")
      (footprint "eagle-import:R1206")
      (libsource (lib "eagle-import") (part "R-EU_R1206"))
    )
    (comp (ref "R171")
      (value "10k")
      (footprint "eagle-import:R1206")
      (libsource (lib "eagle-import") (part "R-EU_R1206"))
    )
    (comp (ref "R172")
      (value "10k")
      (footprint "eagle-import:R1206")
      (libsource (lib "eagle-import") (part "R-EU_R1206"))
    )
    (comp (ref "R173")
      (value "10k")
      (footprint "eagle-import:R1206")
      (libsource (lib "eagle-import") (part "R-EU_R1206"))
    )
    (comp (ref "R174")
      (value "10k")
      (footprint "eagle-import:R1206")
      (libsource (lib "eagle-import") (part "R-EU_R1206"))
    )
    (comp (ref "R175")
      (value "10k")
      (footprint "eagle-import:R1206")
      (libsource (lib "eagle-import") (part "R-EU_R1206"))
    )
    (comp (ref "R176")
      (value "10k")
      (footprint "eagle-import:R1206")
      (libsource (lib "eagle-import") (part "R-EU_R1206"))
    )
    (comp (ref "R177")
      (value "10k")
      (footprint "eagle-import:R1206")
      (libsource (lib "eagle-import") (part "R-EU_R1206"))
    )
    (comp (ref "R178")
      (value "10k")
      (footprint "eagle-import:R1206")
      (libsource (lib "eagle-import") (part "R-EU_R1206"))
    )
    (comp (ref "R179")
      (value "10k")
      (footprint "eagle-import:R1206")
      (libsource (lib "eagle-import") (part "R-EU_R1206"))
    )
    (comp (ref "R180")
      (value "10k")
      (footprint "eagle-import:R1206")
      (libsource (lib "eagle-import") (part "R-EU_R1206"))
    )
    (comp (ref "SOLENOID_CON")
      (value "XT60-M")
      (footprint "eagle-import:AMASS_XT60-M")
      (fields (field (name "MF") "AMASS"))
      (libsource (lib "eagle-import") (part "XT60-M"))
    )
    (comp (ref "SWITCH_CON")
      (value "XT60-M")
      (footprint "eagle-import:AMASS_XT60-M")
      (fields (field (name "MF") "AMASS"))
      (libsource (lib "eagle-import") (part "XT60-M"))
    )
    (comp (ref "TP1")
      (value "PTR1PAD1-13")
      (footprint "eagle-import:P1-13")
      (libsource (lib "eagle-import") (part "PTR1PAD1-13"))
    )
    (comp (ref "TP2")
      (value "PTR1PAD1-13")
      (footprint "eagle-import:P1-13")
      (libsource (lib "eagle-import") (part "PTR1PAD1-13"))
    )
    (comp (ref "TP3")
      (value "PTR1PAD1-13")
      (footprint "eagle-import:P1-13")
      (libsource (lib "eagle-import") (part "PTR1PAD1-13"))
    )
    (comp (ref "TP4")
      (value "PTR1PAD1-13")
      (footprint "eagle-import:P1-13")
      (libsource (lib "eagle-import") (part "PTR1PAD1-13"))
    )
    (comp (ref "TP5")
      (value "PTR1PAD1-13")
      (footprint "eagle-import:P1-13")
      (libsource (lib "eagle-import") (part "PTR1PAD1-13"))
    )
    (comp (ref "TP6")
      (value "PTR1PAD1-13")
      (footprint "eagle-import:P1-13")
      (libsource (lib "eagle-import") (part "PTR1PAD1-13"))
    )
    (comp (ref "TP7")
      (value "PTR1PAD1-13")
      (footprint "eagle-import:P1-13")
      (libsource (lib "eagle-import") (part "PTR1PAD1-13"))
    )
    (comp (ref "TP8")
      (value "PTR1PAD1-13")
      (footprint "eagle-import:P1-13")
      (libsource (lib "eagle-import") (part "PTR1PAD1-13"))
    )
    (comp (ref "TP9")
      (value "PTR1PAD1-13")
      (footprint "eagle-import:P1-13")
      (libsource (lib "eagle-import") (part "PTR1PAD1-13"))
    )
    (comp (ref "TP10")
      (value "PTR1PAD1-13")
      (footprint "eagle-import:P1-13")
      (libsource (lib "eagle-import") (part "PTR1PAD1-13"))
    )
    (comp (ref "TP11")
      (value "PTR1PAD1-13")
      (footprint "eagle-import:P1-13")
      (libsource (lib "eagle-import") (part "PTR1PAD1-13"))
    )
    (comp (ref "TP12")
      (value "PTR1PAD1-13")
      (footprint "eagle-import:P1-13")
      (libsource (lib "eagle-import") (part "PTR1PAD1-13"))
    )
    (comp (ref "TP13")
      (value "PTR1PAD1-13")
      (footprint "eagle-import:P1-13")
      (libsource (lib "eagle-import") (part "PTR1PAD1-13"))
    )
    (comp (ref "TP14")
      (value "PTR1PAD1-13")
      (footprint "eagle-import:P1-13")
      (libsource (lib "eagle-import") (part "PTR1PAD1-13"))
    )
    (comp (ref "TP15")
      (value "PTR1PAD1-13")
      (footprint "eagle-import:P1-13")
      (libsource (lib "eagle-import") (part "PTR1PAD1-13"))
    )
    (comp (ref "TP16")
      (value "PTR1PAD1-13")
      (footprint "eagle-import:P1-13")
      (libsource (lib "eagle-import") (part "PTR1PAD1-13"))
    )
    (comp (ref "TP17")
      (value "PTR1PAD1-13")
      (footprint "eagle-import:P1-13")
      (libsource (lib "eagle-import") (part "PTR1PAD1-13"))
    )
    (comp (ref "TP18")
      (value "PTR1PAD1-13")
      (footprint "eagle-import:P1-13")
      (libsource (lib "eagle-import") (part "PTR1PAD1-13"))
    )
    (comp (ref "TP19")
      (value "PTR1PAD1-13")
      (footprint "eagle-import:P1-13")
      (libsource (lib "eagle-import") (part "PTR1PAD1-13"))
    )
    (comp (ref "TP20")
      (value "PTR1PAD1-13")
      (footprint "eagle-import:P1-13")
      (libsource (lib "eagle-import") (part "PTR1PAD1-13"))
    )
    (comp (ref "TP21")
      (value "PTR1PAD1-13")
      (footprint "eagle-import:P1-13")
      (libsource (lib "eagle-import") (part "PTR1PAD1-13"))
    )
    (comp (ref "TP22")
      (value "PTR1PAD1-13")
      (footprint "eagle-import:P1-13")
      (libsource (lib "eagle-import") (part "PTR1PAD1-13"))
    )
    (comp (ref "TP23")
      (value "PTR1PAD1-13")
      (footprint "eagle-import:P1-13")
      (libsource (lib "eagle-import") (part "PTR1PAD1-13"))
    )
    (comp (ref "TP24")
      (value "PTR1PAD1-13")
      (footprint "eagle-import:P1-13")
      (libsource (lib "eagle-import") (part "PTR1PAD1-13"))
    )
    (comp (ref "TP25")
      (value "PTR1PAD1-13")
      (footprint "eagle-import:P1-13")
      (libsource (lib "eagle-import") (part "PTR1PAD1-13"))
    )
    (comp (ref "TP26")
      (value "PTR1PAD1-13")
      (footprint "eagle-import:P1-13")
      (libsource (lib "eagle-import") (part "PTR1PAD1-13"))
    )
    (comp (ref "TP27")
      (value "PTR1PAD1-13")
      (footprint "eagle-import:P1-13")
      (libsource (lib "eagle-import") (part "PTR1PAD1-13"))
    )
    (comp (ref "TP28")
      (value "PTR1PAD1-13")
      (footprint "eagle-import:P1-13")
      (libsource (lib "eagle-import") (part "PTR1PAD1-13"))
    )
    (comp (ref "TP29")
      (value "PTR1PAD1-13")
      (footprint "eagle-import:P1-13")
      (libsource (lib "eagle-import") (part "PTR1PAD1-13"))
    )
    (comp (ref "TP30")
      (value "PTR1PAD1-13")
      (footprint "eagle-import:P1-13")
      (libsource (lib "eagle-import") (part "PTR1PAD1-13"))
    )
    (comp (ref "TP31")
      (value "PTR1PAD1-13")
      (footprint "eagle-import:P1-13")
      (libsource (lib "eagle-import") (part "PTR1PAD1-13"))
    )
    (comp (ref "TP32")
      (value "PTR1PAD1-13")
      (footprint "eagle-import:P1-13")
      (libsource (lib "eagle-import") (part "PTR1PAD1-13"))
    )
    (comp (ref "U1")
      (value "BH-18650-PC")
      (footprint "eagle-import:BAT_BH-18650-PC")
      (fields (field (name "MF") "MPD"))
      (libsource (lib "eagle-import") (part "BH-18650-PC"))
    )
    (comp (ref "U2")
      (value "BH-18650-PC")
      (footprint "eagle-import:BAT_BH-18650-PC")
      (fields (field (name "MF") "MPD"))
      (libsource (lib "eagle-import") (part "BH-18650-PC"))
    )
    (comp (ref "U3")
      (value "BH-18650-PC")
      (footprint "eagle-import:BAT_BH-18650-PC")
      (fields (field (name "MF") "MPD"))
      (libsource (lib "eagle-import") (part "BH-18650-PC"))
    )
    (comp (ref "U8")
      (value "XL4005")
      (footprint "eagle-import:CONV_XL4015")
      (fields (field (name "MF") "XLSEMI") (field (name "MP") "XL4015"))
      (libsource (lib "eagle-import") (part "XL4015"))
    )
    (comp (ref "U9")
      (value "XL4005")
      (footprint "eagle-import:CONV_XL4015")
      (fields (field (name "MF") "XLSEMI") (field (name "MP") "XL4015"))
      (libsource (lib "eagle-import") (part "XL4015"))
    )
  )
  (nets
    (net (code "1") (name "+3V3") (class "Default")
      (node (ref "C2") (pin "1") (pinfunction "1_1") (pintype "passive"))
      (node (ref "C3") (pin "1") (pinfunction "1_1") (pintype "passive"))
      (node (ref "C4") (pin "1") (pinfunction "1_1") (pintype "passive"))
      (node (ref "C41") (pin "1") (pinfunction "1_1") (pintype "passive"))
      (node (ref "C42") (pin "1") (pinfunction "1_1") (pintype "passive"))
      (node (ref "C43") (pin "1") (pinfunction "1_1") (pintype "passive"))
      (node (ref "C44") (pin "1") (pinfunction "1_1") (pintype "passive"))
      (node (ref "C45") (pin "1") (pinfunction "1_1") (pintype "passive"))
      (node (ref "C46") (pin "1") (pinfunction "1_1") (pintype "passive"))
      (node (ref "C47") (pin "1") (pinfunction "1_1") (pintype "passive"))
      (node (ref "IC1") (pin "24") (pinfunction "VCC_24") (pintype "bidirectional"))
      (node (ref "IC2") (pin "24") (pinfunction "VCC_24") (pintype "bidirectional"))
      (node (ref "IC3") (pin "2") (pinfunction "OUTPUT_2") (pintype "bidirectional"))
      (node (ref "IC3") (pin "4") (pinfunction "VOUT_4") (pintype "bidirectional"))
      (node (ref "J1") (pin "12") (pinfunction "12_12") (pintype "passive"))
      (node (ref "J1") (pin "14") (pinfunction "14_14") (pintype "passive"))
      (node (ref "Q1") (pin "1") (pinfunction "G_1") (pintype "passive"))
      (node (ref "Q10") (pin "1") (pinfunction "G_1") (pintype "passive"))
      (node (ref "Q11") (pin "1") (pinfunction "G_1") (pintype "passive"))
      (node (ref "Q12") (pin "1") (pinfunction "G_1") (pintype "passive"))
      (node (ref "Q13") (pin "1") (pinfunction "G_1") (pintype "passive"))
      (node (ref "Q14") (pin "1") (pinfunction "G_1") (pintype "passive"))
      (node (ref "Q15") (pin "1") (pinfunction "G_1") (pintype "passive"))
      (node (ref "Q16") (pin "1") (pinfunction "G_1") (pintype "passive"))
      (node (ref "Q2") (pin "1") (pinfunction "G_1") (pintype "passive"))
      (node (ref "Q3") (pin "1") (pinfunction "G_1") (pintype "passive"))
      (node (ref "Q4") (pin "1") (pinfunction "G_1") (pintype "passive"))
      (node (ref "Q5") (pin "1") (pinfunction "G_1") (pintype "passive"))
      (node (ref "Q51") (pin "1") (pinfunction "G_1") (pintype "passive"))
      (node (ref "Q52") (pin "1") (pinfunction "G_1") (pintype "passive"))
      (node (ref "Q54") (pin "1") (pinfunction "G_1") (pintype "passive"))
      (node (ref "Q6") (pin "1") (pinfunction "G_1") (pintype "passive"))
      (node (ref "Q7") (pin "1") (pinfunction "G_1") (pintype "passive"))
      (node (ref "Q8") (pin "1") (pinfunction "G_1") (pintype "passive"))
      (node (ref "Q9") (pin "1") (pinfunction "G_1") (pintype "passive"))
      (node (ref "R100") (pin "2") (pinfunction "2_2") (pintype "passive"))
      (node (ref "R110") (pin "2") (pinfunction "2_2") (pintype "passive"))
      (node (ref "R111") (pin "2") (pinfunction "2_2") (pintype "passive"))
      (node (ref "R112") (pin "2") (pinfunction "2_2") (pintype "passive"))
      (node (ref "R113") (pin "2") (pinfunction "2_2") (pintype "passive"))
      (node (ref "R118") (pin "1") (pinfunction "1_1") (pintype "passive"))
      (node (ref "R150") (pin "1") (pinfunction "1_1") (pintype "passive"))
      (node (ref "R151") (pin "1") (pinfunction "1_1") (pintype "passive"))
      (node (ref "R152") (pin "1") (pinfunction "1_1") (pintype "passive"))
      (node (ref "R153") (pin "1") (pinfunction "1_1") (pintype "passive"))
      (node (ref "R154") (pin "1") (pinfunction "1_1") (pintype "passive"))
      (node (ref "R155") (pin "1") (pinfunction "1_1") (pintype "passive"))
      (node (ref "R156") (pin "1") (pinfunction "1_1") (pintype "passive"))
      (node (ref "R157") (pin "1") (pinfunction "1_1") (pintype "passive"))
      (node (ref "R158") (pin "1") (pinfunction "1_1") (pintype "passive"))
      (node (ref "R159") (pin "1") (pinfunction "1_1") (pintype "passive"))
      (node (ref "R160") (pin "1") (pinfunction "1_1") (pintype "passive"))
      (node (ref "R161") (pin "1") (pinfunction "1_1") (pintype "passive"))
      (node (ref "R162") (pin "1") (pinfunction "1_1") (pintype "passive"))
      (node (ref "R163") (pin "1") (pinfunction "1_1") (pintype "passive"))
      (node (ref "R164") (pin "1") (pinfunction "1_1") (pintype "passive"))
      (node (ref "R165") (pin "1") (pinfunction "1_1") (pintype "passive"))
      (node (ref "R166") (pin "1") (pinfunction "1_1") (pintype "passive"))
      (node (ref "R167") (pin "1") (pinfunction "1_1") (pintype "passive"))
      (node (ref "R168") (pin "1") (pinfunction "1_1") (pintype "passive"))
      (node (ref "R169") (pin "1") (pinfunction "1_1") (pintype "passive"))
      (node (ref "R170") (pin "1") (pinfunction "1_1") (pintype "passive"))
      (node (ref "R171") (pin "1") (pinfunction "1_1") (pintype "passive"))
      (node (ref "R172") (pin "1") (pinfunction "1_1") (pintype "passive"))
      (node (ref "R173") (pin "1") (pinfunction "1_1") (pintype "passive"))
      (node (ref "R174") (pin "1") (pinfunction "1_1") (pintype "passive"))
      (node (ref "R175") (pin "1") (pinfunction "1_1") (pintype "passive"))
      (node (ref "R176") (pin "1") (pinfunction "1_1") (pintype "passive"))
      (node (ref "R177") (pin "1") (pinfunction "1_1") (pintype "passive"))
      (node (ref "R178") (pin "1") (pinfunction "1_1") (pintype "passive"))
      (node (ref "R179") (pin "1") (pinfunction "1_1") (pintype "passive"))
      (node (ref "R180") (pin "1") (pinfunction "1_1") (pintype "passive"))
      (node (ref "R2") (pin "2") (pinfunction "2_2") (pintype "passive"))
      (node (ref "R6") (pin "2") (pinfunction "2_2") (pintype "passive"))
      (node (ref "R66") (pin "2") (pinfunction "2_2") (pintype "passive"))
      (node (ref "R67") (pin "2") (pinfunction "2_2") (pintype "passive"))
      (node (ref "R68") (pin "2") (pinfunction "2_2") (pintype "passive"))
      (node (ref "R69") (pin "2") (pinfunction "2_2") (pintype "passive"))
      (node (ref "R8") (pin "2") (pinfunction "2_2") (pintype "passive"))
      (node (ref "R84") (pin "2") (pinfunction "2_2") (pintype "passive"))
      (node (ref "R85") (pin "2") (pinfunction "2_2") (pintype "passive"))
      (node (ref "R86") (pin "2") (pinfunction "2_2") (pintype "passive"))
      (node (ref "R87") (pin "2") (pinfunction "2_2") (pintype "passive"))
      (node (ref "R97") (pin "2") (pinfunction "2_2") (pintype "passive"))
      (node (ref "R98") (pin "2") (pinfunction "2_2") (pintype "passive"))
      (node (ref "R99") (pin "2") (pinfunction "2_2") (pintype "passive"))
    )
    (net (code "2") (name "+5V") (class "Default")
      (node (ref "C1") (pin "1") (pinfunction "1_1") (pintype "passive"))
      (node (ref "C11") (pin "2") (pinfunction "2_2") (pintype "passive"))
      (node (ref "C12") (pin "2") (pinfunction "2_2") (pintype "passive"))
      (node (ref "C15") (pin "2") (pinfunction "2_2") (pintype "passive"))
      (node (ref "C16") (pin "2") (pinfunction "2_2") (pintype "passive"))
      (node (ref "C19") (pin "2") (pinfunction "2_2") (pintype "passive"))
      (node (ref "C20") (pin "2") (pinfunction "2_2") (pintype "passive"))
      (node (ref "C23") (pin "2") (pinfunction "2_2") (pintype "passive"))
      (node (ref "C24") (pin "2") (pinfunction "2_2") (pintype "passive"))
      (node (ref "C27") (pin "2") (pinfunction "2_2") (pintype "passive"))
      (node (ref "C28") (pin "2") (pinfunction "2_2") (pintype "passive"))
      (node (ref "C31") (pin "2") (pinfunction "2_2") (pintype "passive"))
      (node (ref "C32") (pin "2") (pinfunction "2_2") (pintype "passive"))
      (node (ref "C35") (pin "2") (pinfunction "2_2") (pintype "passive"))
      (node (ref "C36") (pin "2") (pinfunction "2_2") (pintype "passive"))
      (node (ref "C39") (pin "2") (pinfunction "2_2") (pintype "passive"))
      (node (ref "C40") (pin "2") (pinfunction "2_2") (pintype "passive"))
      (node (ref "C48") (pin "1") (pinfunction "1_1") (pintype "passive"))
      (node (ref "C53") (pin "1") (pinfunction "1_1") (pintype "passive"))
      (node (ref "C54") (pin "+") (pinfunction "+_+") (pintype "passive"))
      (node (ref "IC3") (pin "3") (pinfunction "INPUT_3") (pintype "bidirectional"))
      (node (ref "L3") (pin "2") (pinfunction "2_2") (pintype "bidirectional"))
      (node (ref "R101") (pin "2") (pinfunction "2_2") (pintype "passive"))
      (node (ref "R102") (pin "2") (pinfunction "2_2") (pintype "passive"))
      (node (ref "R103") (pin "2") (pinfunction "2_2") (pintype "passive"))
      (node (ref "R108") (pin "2") (pinfunction "2_2") (pintype "passive"))
      (node (ref "R109") (pin "2") (pinfunction "2_2") (pintype "passive"))
      (node (ref "R114") (pin "2") (pinfunction "2_2") (pintype "passive"))
      (node (ref "R115") (pin "2") (pinfunction "2_2") (pintype "passive"))
      (node (ref "R116") (pin "2") (pinfunction "2_2") (pintype "passive"))
      (node (ref "R134") (pin "2") (pinfunction "2_2") (pintype "passive"))
      (node (ref "R135") (pin "2") (pinfunction "2_2") (pintype "passive"))
      (node (ref "R136") (pin "2") (pinfunction "2_2") (pintype "passive"))
      (node (ref "R137") (pin "2") (pinfunction "2_2") (pintype "passive"))
      (node (ref "R138") (pin "2") (pinfunction "2_2") (pintype "passive"))
      (node (ref "R139") (pin "2") (pinfunction "2_2") (pintype "passive"))
      (node (ref "R140") (pin "2") (pinfunction "2_2") (pintype "passive"))
      (node (ref "R141") (pin "2") (pinfunction "2_2") (pintype "passive"))
      (node (ref "R142") (pin "2") (pinfunction "2_2") (pintype "passive"))
      (node (ref "R143") (pin "2") (pinfunction "2_2") (pintype "passive"))
      (node (ref "R144") (pin "2") (pinfunction "2_2") (pintype "passive"))
      (node (ref "R145") (pin "2") (pinfunction "2_2") (pintype "passive"))
      (node (ref "R146") (pin "2") (pinfunction "2_2") (pintype "passive"))
      (node (ref "R147") (pin "2") (pinfunction "2_2") (pintype "passive"))
      (node (ref "R148") (pin "2") (pinfunction "2_2") (pintype "passive"))
      (node (ref "R149") (pin "2") (pinfunction "2_2") (pintype "passive"))
      (node (ref "R4") (pin "3") (pinfunction "A_3") (pintype "passive"))
      (node (ref "R65") (pin "2") (pinfunction "2_2") (pintype "passive"))
      (node (ref "R7") (pin "2") (pinfunction "2_2") (pintype "passive"))
      (node (ref "R74") (pin "2") (pinfunction "2_2") (pintype "passive"))
      (node (ref "R75") (pin "2") (pinfunction "2_2") (pintype "passive"))
      (node (ref "R76") (pin "2") (pinfunction "2_2") (pintype "passive"))
      (node (ref "R77") (pin "2") (pinfunction "2_2") (pintype "passive"))
      (node (ref "R82") (pin "2") (pinfunction "2_2") (pintype "passive"))
      (node (ref "R83") (pin "2") (pinfunction "2_2") (pintype "passive"))
      (node (ref "R88") (pin "2") (pinfunction "2_2") (pintype "passive"))
      (node (ref "R89") (pin "2") (pinfunction "2_2") (pintype "passive"))
      (node (ref "R90") (pin "2") (pinfunction "2_2") (pintype "passive"))
      (node (ref "R95") (pin "2") (pinfunction "2_2") (pintype "passive"))
      (node (ref "R96") (pin "2") (pinfunction "2_2") (pintype "passive"))
    )
    (net (code "3") (name "+5V_UP") (class "Default")
      (node (ref "C10") (pin "2") (pinfunction "2_2") (pintype "passive"))
      (node (ref "C13") (pin "2") (pinfunction "2_2") (pintype "passive"))
      (node (ref "C14") (pin "2") (pinfunction "2_2") (pintype "passive"))
      (node (ref "C17") (pin "2") (pinfunction "2_2") (pintype "passive"))
      (node (ref "C18") (pin "2") (pinfunction "2_2") (pintype "passive"))
      (node (ref "C21") (pin "2") (pinfunction "2_2") (pintype "passive"))
      (node (ref "C22") (pin "2") (pinfunction "2_2") (pintype "passive"))
      (node (ref "C25") (pin "2") (pinfunction "2_2") (pintype "passive"))
      (node (ref "C26") (pin "2") (pinfunction "2_2") (pintype "passive"))
      (node (ref "C29") (pin "2") (pinfunction "2_2") (pintype "passive"))
      (node (ref "C30") (pin "2") (pinfunction "2_2") (pintype "passive"))
      (node (ref "C33") (pin "2") (pinfunction "2_2") (pintype "passive"))
      (node (ref "C34") (pin "2") (pinfunction "2_2") (pintype "passive"))
      (node (ref "C37") (pin "2") (pinfunction "2_2") (pintype "passive"))
      (node (ref "C38") (pin "2") (pinfunction "2_2") (pintype "passive"))
      (node (ref "C50") (pin "1") (pinfunction "1_1") (pintype "passive"))
      (node (ref "C51") (pin "+") (pinfunction "+_+") (pintype "passive"))
      (node (ref "C9") (pin "2") (pinfunction "2_2") (pintype "passive"))
      (node (ref "L2") (pin "2") (pinfunction "2_2") (pintype "bidirectional"))
      (node (ref "R117") (pin "2") (pinfunction "2_2") (pintype "passive"))
      (node (ref "R119") (pin "2") (pinfunction "2_2") (pintype "passive"))
      (node (ref "R120") (pin "2") (pinfunction "2_2") (pintype "passive"))
      (node (ref "R121") (pin "2") (pinfunction "2_2") (pintype "passive"))
      (node (ref "R122") (pin "2") (pinfunction "2_2") (pintype "passive"))
      (node (ref "R123") (pin "2") (pinfunction "2_2") (pintype "passive"))
      (node (ref "R124") (pin "2") (pinfunction "2_2") (pintype "passive"))
      (node (ref "R125") (pin "2") (pinfunction "2_2") (pintype "passive"))
      (node (ref "R126") (pin "2") (pinfunction "2_2") (pintype "passive"))
      (node (ref "R127") (pin "2") (pinfunction "2_2") (pintype "passive"))
      (node (ref "R128") (pin "2") (pinfunction "2_2") (pintype "passive"))
      (node (ref "R129") (pin "2") (pinfunction "2_2") (pintype "passive"))
      (node (ref "R130") (pin "2") (pinfunction "2_2") (pintype "passive"))
      (node (ref "R131") (pin "2") (pinfunction "2_2") (pintype "passive"))
      (node (ref "R132") (pin "2") (pinfunction "2_2") (pintype "passive"))
      (node (ref "R133") (pin "2") (pinfunction "2_2") (pintype "passive"))
      (node (ref "R3") (pin "3") (pinfunction "A_3") (pintype "passive"))
      (node (ref "R5") (pin "2") (pinfunction "2_2") (pintype "passive"))
    )
    (net (code "4") (name "+5_UP") (class "Default")
      (node (ref "J1") (pin "16") (pinfunction "16_16") (pintype "passive"))
      (node (ref "J1") (pin "18") (pinfunction "18_18") (pintype "passive"))
      (node (ref "J1") (pin "20") (pinfunction "20_20") (pintype "passive"))
      (node (ref "J1") (pin "22") (pinfunction "22_22") (pintype "passive"))
      (node (ref "J1") (pin "24") (pinfunction "24_24") (pintype "passive"))
      (node (ref "J1") (pin "26") (pinfunction "26_26") (pintype "passive"))
    )
    (net (code "5") (name "+12V") (class "Default")
      (node (ref "C49") (pin "+") (pinfunction "+_+") (pintype "passive"))
      (node (ref "C5") (pin "+") (pinfunction "+_+") (pintype "passive"))
      (node (ref "C6") (pin "+") (pinfunction "+_+") (pintype "passive"))
      (node (ref "C7") (pin "+") (pinfunction "+_+") (pintype "passive"))
      (node (ref "C8") (pin "+") (pinfunction "+_+") (pintype "passive"))
      (node (ref "J1") (pin "10") (pinfunction "10_10") (pintype "passive"))
      (node (ref "MOTOR_A_DRV") (pin "P$13") (pinfunction "VCC_P$13") (pintype "power_in"))
      (node (ref "MOTOR_A_DRV") (pin "P$23") (pinfunction "VCC_P$23") (pintype "power_in"))
      (node (ref "MOTOR_A_DRV") (pin "P$3") (pinfunction "VCC_P$3") (pintype "power_in"))
      (node (ref "MOTOR_B_DRV") (pin "P$13") (pinfunction "VCC_P$13") (pintype "power_in"))
      (node (ref "MOTOR_B_DRV") (pin "P$23") (pinfunction "VCC_P$23") (pintype "power_in"))
      (node (ref "MOTOR_B_DRV") (pin "P$3") (pinfunction "VCC_P$3") (pintype "power_in"))
      (node (ref "MOTOR_C_DRV") (pin "P$13") (pinfunction "VCC_P$13") (pintype "power_in"))
      (node (ref "MOTOR_C_DRV") (pin "P$23") (pinfunction "VCC_P$23") (pintype "power_in"))
      (node (ref "MOTOR_C_DRV") (pin "P$3") (pinfunction "VCC_P$3") (pintype "power_in"))
      (node (ref "MOTOR_D_DRV") (pin "P$13") (pinfunction "VCC_P$13") (pintype "power_in"))
      (node (ref "MOTOR_D_DRV") (pin "P$23") (pinfunction "VCC_P$23") (pintype "power_in"))
      (node (ref "MOTOR_D_DRV") (pin "P$3") (pinfunction "VCC_P$3") (pintype "power_in"))
      (node (ref "R1") (pin "2") (pinfunction "2_2") (pintype "passive"))
      (node (ref "SOLENOID_CON") (pin "P") (pinfunction "POS_P") (pintype "passive"))
      (node (ref "U2") (pin "P") (pinfunction "+_P") (pintype "passive"))
      (node (ref "U8") (pin "4") (pinfunction "EN_4") (pintype "passive"))
      (node (ref "U8") (pin "5") (pinfunction "VIN_5") (pintype "input"))
      (node (ref "U9") (pin "4") (pinfunction "EN_4") (pintype "passive"))
      (node (ref "U9") (pin "5") (pinfunction "VIN_5") (pintype "input"))
    )
    (net (code "6") (name "EN_A") (class "Default")
      (node (ref "J1") (pin "03") (pinfunction "03_03") (pintype "passive"))
      (node (ref "Q9") (pin "2") (pinfunction "S_2") (pintype "passive"))
      (node (ref "R97") (pin "1") (pinfunction "1_1") (pintype "passive"))
    )
    (net (code "7") (name "EN_B") (class "Default")
      (node (ref "J1") (pin "11") (pinfunction "11_11") (pintype "passive"))
      (node (ref "Q1") (pin "2") (pinfunction "S_2") (pintype "passive"))
      (node (ref "R66") (pin "1") (pinfunction "1_1") (pintype "passive"))
    )
    (net (code "8") (name "EN_C") (class "Default")
      (node (ref "J1") (pin "19") (pinfunction "19_19") (pintype "passive"))
      (node (ref "Q13") (pin "2") (pinfunction "S_2") (pintype "passive"))
      (node (ref "R110") (pin "1") (pinfunction "1_1") (pintype "passive"))
    )
    (net (code "9") (name "EN_D") (class "Default")
      (node (ref "J1") (pin "27") (pinfunction "27_27") (pintype "passive"))
      (node (ref "Q5") (pin "2") (pinfunction "S_2") (pintype "passive"))
      (node (ref "R84") (pin "1") (pinfunction "1_1") (pintype "passive"))
    )
    (net (code "10") (name "GND") (class "Default")
      (node (ref "C1") (pin "2") (pinfunction "2_2") (pintype "passive"))
      (node (ref "C2") (pin "2") (pinfunction "2_2") (pintype "passive"))
      (node (ref "C3") (pin "2") (pinfunction "2_2") (pintype "passive"))
      (node (ref "C4") (pin "2") (pinfunction "2_2") (pintype "passive"))
      (node (ref "C41") (pin "2") (pinfunction "2_2") (pintype "passive"))
      (node (ref "C42") (pin "2") (pinfunction "2_2") (pintype "passive"))
      (node (ref "C43") (pin "2") (pinfunction "2_2") (pintype "passive"))
      (node (ref "C44") (pin "2") (pinfunction "2_2") (pintype "passive"))
      (node (ref "C45") (pin "2") (pinfunction "2_2") (pintype "passive"))
      (node (ref "C46") (pin "2") (pinfunction "2_2") (pintype "passive"))
      (node (ref "C47") (pin "2") (pinfunction "2_2") (pintype "passive"))
      (node (ref "C48") (pin "2") (pinfunction "2_2") (pintype "passive"))
      (node (ref "C49") (pin "-") (pinfunction "-_-") (pintype "passive"))
      (node (ref "C5") (pin "-") (pinfunction "-_-") (pintype "passive"))
      (node (ref "C51") (pin "-") (pinfunction "-_-") (pintype "passive"))
      (node (ref "C54") (pin "-") (pinfunction "-_-") (pintype "passive"))
      (node (ref "C6") (pin "-") (pinfunction "-_-") (pintype "passive"))
      (node (ref "C7") (pin "-") (pinfunction "-_-") (pintype "passive"))
      (node (ref "C8") (pin "-") (pinfunction "-_-") (pintype "passive"))
      (node (ref "D34") (pin "2") (pinfunction "A_2") (pintype "bidirectional"))
      (node (ref "D35") (pin "2") (pinfunction "A_2") (pintype "bidirectional"))
      (node (ref "IC1") (pin "12") (pinfunction "GND_12") (pintype "bidirectional"))
      (node (ref "IC1") (pin "15") (pinfunction "~{E}_15") (pintype "bidirectional"))
      (node (ref "IC2") (pin "12") (pinfunction "GND_12") (pintype "bidirectional"))
      (node (ref "IC2") (pin "15") (pinfunction "~{E}_15") (pintype "bidirectional"))
      (node (ref "IC3") (pin "1") (pinfunction "ADJ/GND_1") (pintype "bidirectional"))
      (node (ref "J1") (pin "28") (pinfunction "28_28") (pintype "passive"))
      (node (ref "J1") (pin "30") (pinfunction "30_30") (pintype "passive"))
      (node (ref "J1") (pin "32") (pinfunction "32_32") (pintype "passive"))
      (node (ref "J1") (pin "34") (pinfunction "34_34") (pintype "passive"))
      (node (ref "J1") (pin "36") (pinfunction "36_36") (pintype "passive"))
      (node (ref "J1") (pin "38") (pinfunction "38_38") (pintype "passive"))
      (node (ref "J1") (pin "40") (pinfunction "40_40") (pintype "passive"))
      (node (ref "MOTOR_A_DRV") (pin "P$18") (pinfunction "GND_P$18") (pintype "power_in"))
      (node (ref "MOTOR_A_DRV") (pin "P$19") (pinfunction "GND_P$19") (pintype "power_in"))
      (node (ref "MOTOR_A_DRV") (pin "P$20") (pinfunction "GND_P$20") (pintype "power_in"))
      (node (ref "MOTOR_A_DRV") (pin "P$26") (pinfunction "GND_P$26") (pintype "power_in"))
      (node (ref "MOTOR_A_DRV") (pin "P$27") (pinfunction "GND_P$27") (pintype "power_in"))
      (node (ref "MOTOR_A_DRV") (pin "P$28") (pinfunction "GND_P$28") (pintype "power_in"))
      (node (ref "MOTOR_B_DRV") (pin "P$18") (pinfunction "GND_P$18") (pintype "power_in"))
      (node (ref "MOTOR_B_DRV") (pin "P$19") (pinfunction "GND_P$19") (pintype "power_in"))
      (node (ref "MOTOR_B_DRV") (pin "P$20") (pinfunction "GND_P$20") (pintype "power_in"))
      (node (ref "MOTOR_B_DRV") (pin "P$26") (pinfunction "GND_P$26") (pintype "power_in"))
      (node (ref "MOTOR_B_DRV") (pin "P$27") (pinfunction "GND_P$27") (pintype "power_in"))
      (node (ref "MOTOR_B_DRV") (pin "P$28") (pinfunction "GND_P$28") (pintype "power_in"))
      (node (ref "MOTOR_C_DRV") (pin "P$18") (pinfunction "GND_P$18") (pintype "power_in"))
      (node (ref "MOTOR_C_DRV") (pin "P$19") (pinfunction "GND_P$19") (pintype "power_in"))
      (node (ref "MOTOR_C_DRV") (pin "P$20") (pinfunction "GND_P$20") (pintype "power_in"))
      (node (ref "MOTOR_C_DRV") (pin "P$26") (pinfunction "GND_P$26") (pintype "power_in"))
      (node (ref "MOTOR_C_DRV") (pin "P$27") (pinfunction "GND_P$27") (pintype "power_in"))
      (node (ref "MOTOR_C_DRV") (pin "P$28") (pinfunction "GND_P$28") (pintype "power_in"))
      (node (ref "MOTOR_D_DRV") (pin "P$18") (pinfunction "GND_P$18") (pintype "power_in"))
      (node (ref "MOTOR_D_DRV") (pin "P$19") (pinfunction "GND_P$19") (pintype "power_in"))
      (node (ref "MOTOR_D_DRV") (pin "P$20") (pinfunction "GND_P$20") (pintype "power_in"))
      (node (ref "MOTOR_D_DRV") (pin "P$26") (pinfunction "GND_P$26") (pintype "power_in"))
      (node (ref "MOTOR_D_DRV") (pin "P$27") (pinfunction "GND_P$27") (pintype "power_in"))
      (node (ref "MOTOR_D_DRV") (pin "P$28") (pinfunction "GND_P$28") (pintype "power_in"))
      (node (ref "Q17") (pin "E") (pinfunction "E_E") (pintype "passive"))
      (node (ref "Q18") (pin "E") (pinfunction "E_E") (pintype "passive"))
      (node (ref "Q19") (pin "E") (pinfunction "E_E") (pintype "passive"))
      (node (ref "Q20") (pin "E") (pinfunction "E_E") (pintype "passive"))
      (node (ref "Q21") (pin "E") (pinfunction "E_E") (pintype "passive"))
      (node (ref "Q22") (pin "E") (pinfunction "E_E") (pintype "passive"))
      (node (ref "Q23") (pin "E") (pinfunction "E_E") (pintype "passive"))
      (node (ref "Q24") (pin "E") (pinfunction "E_E") (pintype "passive"))
      (node (ref "Q25") (pin "E") (pinfunction "E_E") (pintype "passive"))
      (node (ref "Q26") (pin "E") (pinfunction "E_E") (pintype "passive"))
      (node (ref "Q27") (pin "E") (pinfunction "E_E") (pintype "passive"))
      (node (ref "Q28") (pin "E") (pinfunction "E_E") (pintype "passive"))
      (node (ref "Q29") (pin "E") (pinfunction "E_E") (pintype "passive"))
      (node (ref "Q30") (pin "E") (pinfunction "E_E") (pintype "passive"))
      (node (ref "Q31") (pin "E") (pinfunction "E_E") (pintype "passive"))
      (node (ref "Q32") (pin "E") (pinfunction "E_E") (pintype "passive"))
      (node (ref "Q33") (pin "E") (pinfunction "E_E") (pintype "passive"))
      (node (ref "Q34") (pin "E") (pinfunction "E_E") (pintype "passive"))
      (node (ref "Q35") (pin "E") (pinfunction "E_E") (pintype "passive"))
      (node (ref "Q36") (pin "E") (pinfunction "E_E") (pintype "passive"))
      (node (ref "Q37") (pin "E") (pinfunction "E_E") (pintype "passive"))
      (node (ref "Q38") (pin "E") (pinfunction "E_E") (pintype "passive"))
      (node (ref "Q39") (pin "E") (pinfunction "E_E") (pintype "passive"))
      (node (ref "Q40") (pin "E") (pinfunction "E_E") (pintype "passive"))
      (node (ref "Q41") (pin "E") (pinfunction "E_E") (pintype "passive"))
      (node (ref "Q42") (pin "E") (pinfunction "E_E") (pintype "passive"))
      (node (ref "Q43") (pin "E") (pinfunction "E_E") (pintype "passive"))
      (node (ref "Q44") (pin "E") (pinfunction "E_E") (pintype "passive"))
      (node (ref "Q45") (pin "E") (pinfunction "E_E") (pintype "passive"))
      (node (ref "Q46") (pin "E") (pinfunction "E_E") (pintype "passive"))
      (node (ref "Q47") (pin "E") (pinfunction "E_E") (pintype "passive"))
      (node (ref "Q48") (pin "E") (pinfunction "E_E") (pintype "passive"))
      (node (ref "Q49") (pin "3") (pinfunction "S_3") (pintype "passive"))
      (node (ref "Q50") (pin "3") (pinfunction "S_3") (pintype "passive"))
      (node (ref "Q53") (pin "3") (pinfunction "S_3") (pintype "passive"))
      (node (ref "R107") (pin "2") (pinfunction "2_2") (pintype "passive"))
      (node (ref "R3") (pin "1") (pinfunction "E_1") (pintype "passive"))
      (node (ref "R4") (pin "1") (pinfunction "E_1") (pintype "passive"))
      (node (ref "R73") (pin "2") (pinfunction "2_2") (pintype "passive"))
      (node (ref "R81") (pin "2") (pinfunction "2_2") (pintype "passive"))
      (node (ref "R94") (pin "2") (pinfunction "2_2") (pintype "passive"))
      (node (ref "SWITCH_CON") (pin "N") (pinfunction "NEG_N") (pintype "passive"))
      (node (ref "U8") (pin "1") (pinfunction "GND_1") (pintype "power_in"))
      (node (ref "U9") (pin "1") (pinfunction "GND_1") (pintype "power_in"))
    )
    (net (code "11") (name "IN1_A") (class "Default")
      (node (ref "J1") (pin "05") (pinfunction "05_05") (pintype "passive"))
      (node (ref "Q10") (pin "2") (pinfunction "S_2") (pintype "passive"))
      (node (ref "R98") (pin "1") (pinfunction "1_1") (pintype "passive"))
    )
    (net (code "12") (name "IN1_B") (class "Default")
      (node (ref "J1") (pin "13") (pinfunction "13_13") (pintype "passive"))
      (node (ref "Q2") (pin "2") (pinfunction "S_2") (pintype "passive"))
      (node (ref "R67") (pin "1") (pinfunction "1_1") (pintype "passive"))
    )
    (net (code "13") (name "IN1_C") (class "Default")
      (node (ref "J1") (pin "21") (pinfunction "21_21") (pintype "passive"))
      (node (ref "Q14") (pin "2") (pinfunction "S_2") (pintype "passive"))
      (node (ref "R111") (pin "1") (pinfunction "1_1") (pintype "passive"))
    )
    (net (code "14") (name "IN1_D") (class "Default")
      (node (ref "J1") (pin "29") (pinfunction "29_29") (pintype "passive"))
      (node (ref "Q6") (pin "2") (pinfunction "S_2") (pintype "passive"))
      (node (ref "R85") (pin "1") (pinfunction "1_1") (pintype "passive"))
    )
    (net (code "15") (name "IN2_A") (class "Default")
      (node (ref "J1") (pin "07") (pinfunction "07_07") (pintype "passive"))
      (node (ref "Q11") (pin "2") (pinfunction "S_2") (pintype "passive"))
      (node (ref "R99") (pin "1") (pinfunction "1_1") (pintype "passive"))
    )
    (net (code "16") (name "IN2_B") (class "Default")
      (node (ref "J1") (pin "15") (pinfunction "15_15") (pintype "passive"))
      (node (ref "Q3") (pin "2") (pinfunction "S_2") (pintype "passive"))
      (node (ref "R68") (pin "1") (pinfunction "1_1") (pintype "passive"))
    )
    (net (code "17") (name "IN2_C") (class "Default")
      (node (ref "J1") (pin "23") (pinfunction "23_23") (pintype "passive"))
      (node (ref "Q15") (pin "2") (pinfunction "S_2") (pintype "passive"))
      (node (ref "R112") (pin "1") (pinfunction "1_1") (pintype "passive"))
    )
    (net (code "18") (name "IN2_D") (class "Default")
      (node (ref "J1") (pin "31") (pinfunction "31_31") (pintype "passive"))
      (node (ref "Q7") (pin "2") (pinfunction "S_2") (pintype "passive"))
      (node (ref "R86") (pin "1") (pinfunction "1_1") (pintype "passive"))
    )
    (net (code "19") (name "KICKER") (class "Default")
      (node (ref "J1") (pin "01") (pinfunction "01_01") (pintype "passive"))
      (node (ref "Q51") (pin "2") (pinfunction "S_2") (pintype "passive"))
      (node (ref "R2") (pin "1") (pinfunction "1_1") (pintype "passive"))
    )
    (net (code "20") (name "LED_ENABLE") (class "Default")
      (node (ref "J1") (pin "08") (pinfunction "08_08") (pintype "passive"))
      (node (ref "Q52") (pin "2") (pinfunction "S_2") (pintype "passive"))
      (node (ref "Q54") (pin "2") (pinfunction "S_2") (pintype "passive"))
      (node (ref "R6") (pin "1") (pinfunction "1_1") (pintype "passive"))
      (node (ref "R8") (pin "1") (pinfunction "1_1") (pintype "passive"))
    )
    (net (code "21") (name "LIGHT_I0") (class "Default")
      (node (ref "IC1") (pin "9") (pinfunction "I0_9") (pintype "bidirectional"))
      (node (ref "Q17") (pin "C") (pinfunction "C_C") (pintype "passive"))
      (node (ref "R118") (pin "2") (pinfunction "2_2") (pintype "passive"))
      (node (ref "TP1") (pin "TP") (pinfunction "TP_TP") (pintype "input"))
    )
    (net (code "22") (name "LIGHT_I1") (class "Default")
      (node (ref "IC1") (pin "8") (pinfunction "I1_8") (pintype "bidirectional"))
      (node (ref "Q18") (pin "C") (pinfunction "C_C") (pintype "passive"))
      (node (ref "R150") (pin "2") (pinfunction "2_2") (pintype "passive"))
      (node (ref "TP2") (pin "TP") (pinfunction "TP_TP") (pintype "input"))
    )
    (net (code "23") (name "LIGHT_I2") (class "Default")
      (node (ref "IC1") (pin "7") (pinfunction "I2_7") (pintype "bidirectional"))
      (node (ref "Q19") (pin "C") (pinfunction "C_C") (pintype "passive"))
      (node (ref "R151") (pin "2") (pinfunction "2_2") (pintype "passive"))
      (node (ref "TP3") (pin "TP") (pinfunction "TP_TP") (pintype "input"))
    )
    (net (code "24") (name "LIGHT_I3") (class "Default")
      (node (ref "IC1") (pin "6") (pinfunction "I3_6") (pintype "bidirectional"))
      (node (ref "Q20") (pin "C") (pinfunction "C_C") (pintype "passive"))
      (node (ref "R152") (pin "2") (pinfunction "2_2") (pintype "passive"))
      (node (ref "TP4") (pin "TP") (pinfunction "TP_TP") (pintype "input"))
    )
    (net (code "25") (name "LIGHT_I4") (class "Default")
      (node (ref "IC1") (pin "5") (pinfunction "I4_5") (pintype "bidirectional"))
      (node (ref "Q21") (pin "C") (pinfunction "C_C") (pintype "passive"))
      (node (ref "R153") (pin "2") (pinfunction "2_2") (pintype "passive"))
      (node (ref "TP5") (pin "TP") (pinfunction "TP_TP") (pintype "input"))
    )
    (net (code "26") (name "LIGHT_I5") (class "Default")
      (node (ref "IC1") (pin "4") (pinfunction "I5_4") (pintype "bidirectional"))
      (node (ref "Q22") (pin "C") (pinfunction "C_C") (pintype "passive"))
      (node (ref "R154") (pin "2") (pinfunction "2_2") (pintype "passive"))
      (node (ref "TP6") (pin "TP") (pinfunction "TP_TP") (pintype "input"))
    )
    (net (code "27") (name "LIGHT_I6") (class "Default")
      (node (ref "IC1") (pin "3") (pinfunction "I6_3") (pintype "bidirectional"))
      (node (ref "Q23") (pin "C") (pinfunction "C_C") (pintype "passive"))
      (node (ref "R155") (pin "2") (pinfunction "2_2") (pintype "passive"))
      (node (ref "TP7") (pin "TP") (pinfunction "TP_TP") (pintype "input"))
    )
    (net (code "28") (name "LIGHT_I7") (class "Default")
      (node (ref "IC1") (pin "2") (pinfunction "I7_2") (pintype "bidirectional"))
      (node (ref "Q24") (pin "C") (pinfunction "C_C") (pintype "passive"))
      (node (ref "R156") (pin "2") (pinfunction "2_2") (pintype "passive"))
      (node (ref "TP8") (pin "TP") (pinfunction "TP_TP") (pintype "input"))
    )
    (net (code "29") (name "LIGHT_I8") (class "Default")
      (node (ref "IC1") (pin "23") (pinfunction "I8_23") (pintype "bidirectional"))
      (node (ref "Q25") (pin "C") (pinfunction "C_C") (pintype "passive"))
      (node (ref "R157") (pin "2") (pinfunction "2_2") (pintype "passive"))
      (node (ref "TP9") (pin "TP") (pinfunction "TP_TP") (pintype "input"))
    )
    (net (code "30") (name "LIGHT_I9") (class "Default")
      (node (ref "IC1") (pin "22") (pinfunction "I9_22") (pintype "bidirectional"))
      (node (ref "Q26") (pin "C") (pinfunction "C_C") (pintype "passive"))
      (node (ref "R158") (pin "2") (pinfunction "2_2") (pintype "passive"))
      (node (ref "TP10") (pin "TP") (pinfunction "TP_TP") (pintype "input"))
    )
    (net (code "31") (name "LIGHT_I10") (class "Default")
      (node (ref "IC1") (pin "21") (pinfunction "I10_21") (pintype "bidirectional"))
      (node (ref "Q27") (pin "C") (pinfunction "C_C") (pintype "passive"))
      (node (ref "R159") (pin "2") (pinfunction "2_2") (pintype "passive"))
      (node (ref "TP11") (pin "TP") (pinfunction "TP_TP") (pintype "input"))
    )
    (net (code "32") (name "LIGHT_I11") (class "Default")
      (node (ref "IC1") (pin "20") (pinfunction "I11_20") (pintype "bidirectional"))
      (node (ref "Q28") (pin "C") (pinfunction "C_C") (pintype "passive"))
      (node (ref "R160") (pin "2") (pinfunction "2_2") (pintype "passive"))
      (node (ref "TP12") (pin "TP") (pinfunction "TP_TP") (pintype "input"))
    )
    (net (code "33") (name "LIGHT_I12") (class "Default")
      (node (ref "IC1") (pin "19") (pinfunction "I12_19") (pintype "bidirectional"))
      (node (ref "Q29") (pin "C") (pinfunction "C_C") (pintype "passive"))
      (node (ref "R161") (pin "2") (pinfunction "2_2") (pintype "passive"))
      (node (ref "TP13") (pin "TP") (pinfunction "TP_TP") (pintype "input"))
    )
    (net (code "34") (name "LIGHT_I13") (class "Default")
      (node (ref "IC1") (pin "18") (pinfunction "I13_18") (pintype "bidirectional"))
      (node (ref "Q30") (pin "C") (pinfunction "C_C") (pintype "passive"))
      (node (ref "R162") (pin "2") (pinfunction "2_2") (pintype "passive"))
      (node (ref "TP14") (pin "TP") (pinfunction "TP_TP") (pintype "input"))
    )
    (net (code "35") (name "LIGHT_I14") (class "Default")
      (node (ref "IC1") (pin "17") (pinfunction "I14_17") (pintype "bidirectional"))
      (node (ref "Q31") (pin "C") (pinfunction "C_C") (pintype "passive"))
      (node (ref "R163") (pin "2") (pinfunction "2_2") (pintype "passive"))
      (node (ref "TP15") (pin "TP") (pinfunction "TP_TP") (pintype "input"))
    )
    (net (code "36") (name "LIGHT_I15") (class "Default")
      (node (ref "IC1") (pin "16") (pinfunction "I15_16") (pintype "bidirectional"))
      (node (ref "Q32") (pin "C") (pinfunction "C_C") (pintype "passive"))
      (node (ref "R164") (pin "2") (pinfunction "2_2") (pintype "passive"))
      (node (ref "TP16") (pin "TP") (pinfunction "TP_TP") (pintype "input"))
    )
    (net (code "37") (name "LIGHT_I16") (class "Default")
      (node (ref "IC2") (pin "9") (pinfunction "I0_9") (pintype "bidirectional"))
      (node (ref "Q33") (pin "C") (pinfunction "C_C") (pintype "passive"))
      (node (ref "R165") (pin "2") (pinfunction "2_2") (pintype "passive"))
      (node (ref "TP17") (pin "TP") (pinfunction "TP_TP") (pintype "input"))
    )
    (net (code "38") (name "LIGHT_I17") (class "Default")
      (node (ref "IC2") (pin "8") (pinfunction "I1_8") (pintype "bidirectional"))
      (node (ref "Q34") (pin "C") (pinfunction "C_C") (pintype "passive"))
      (node (ref "R166") (pin "2") (pinfunction "2_2") (pintype "passive"))
      (node (ref "TP18") (pin "TP") (pinfunction "TP_TP") (pintype "input"))
    )
    (net (code "39") (name "LIGHT_I18") (class "Default")
      (node (ref "IC2") (pin "7") (pinfunction "I2_7") (pintype "bidirectional"))
      (node (ref "Q35") (pin "C") (pinfunction "C_C") (pintype "passive"))
      (node (ref "R167") (pin "2") (pinfunction "2_2") (pintype "passive"))
      (node (ref "TP19") (pin "TP") (pinfunction "TP_TP") (pintype "input"))
    )
    (net (code "40") (name "LIGHT_I19") (class "Default")
      (node (ref "IC2") (pin "6") (pinfunction "I3_6") (pintype "bidirectional"))
      (node (ref "Q36") (pin "C") (pinfunction "C_C") (pintype "passive"))
      (node (ref "R168") (pin "2") (pinfunction "2_2") (pintype "passive"))
      (node (ref "TP20") (pin "TP") (pinfunction "TP_TP") (pintype "input"))
    )
    (net (code "41") (name "LIGHT_I20") (class "Default")
      (node (ref "IC2") (pin "5") (pinfunction "I4_5") (pintype "bidirectional"))
      (node (ref "Q37") (pin "C") (pinfunction "C_C") (pintype "passive"))
      (node (ref "R169") (pin "2") (pinfunction "2_2") (pintype "passive"))
      (node (ref "TP21") (pin "TP") (pinfunction "TP_TP") (pintype "input"))
    )
    (net (code "42") (name "LIGHT_I21") (class "Default")
      (node (ref "IC2") (pin "4") (pinfunction "I5_4") (pintype "bidirectional"))
      (node (ref "Q38") (pin "C") (pinfunction "C_C") (pintype "passive"))
      (node (ref "R170") (pin "2") (pinfunction "2_2") (pintype "passive"))
      (node (ref "TP22") (pin "TP") (pinfunction "TP_TP") (pintype "input"))
    )
    (net (code "43") (name "LIGHT_I22") (class "Default")
      (node (ref "IC2") (pin "3") (pinfunction "I6_3") (pintype "bidirectional"))
      (node (ref "Q39") (pin "C") (pinfunction "C_C") (pintype "passive"))
      (node (ref "R171") (pin "2") (pinfunction "2_2") (pintype "passive"))
      (node (ref "TP23") (pin "TP") (pinfunction "TP_TP") (pintype "input"))
    )
    (net (code "44") (name "LIGHT_I23") (class "Default")
      (node (ref "IC2") (pin "2") (pinfunction "I7_2") (pintype "bidirectional"))
      (node (ref "Q40") (pin "C") (pinfunction "C_C") (pintype "passive"))
      (node (ref "R172") (pin "2") (pinfunction "2_2") (pintype "passive"))
      (node (ref "TP24") (pin "TP") (pinfunction "TP_TP") (pintype "input"))
    )
    (net (code "45") (name "LIGHT_I24") (class "Default")
      (node (ref "IC2") (pin "23") (pinfunction "I8_23") (pintype "bidirectional"))
      (node (ref "Q41") (pin "C") (pinfunction "C_C") (pintype "passive"))
      (node (ref "R173") (pin "2") (pinfunction "2_2") (pintype "passive"))
      (node (ref "TP25") (pin "TP") (pinfunction "TP_TP") (pintype "input"))
    )
    (net (code "46") (name "LIGHT_I25") (class "Default")
      (node (ref "IC2") (pin "22") (pinfunction "I9_22") (pintype "bidirectional"))
      (node (ref "Q42") (pin "C") (pinfunction "C_C") (pintype "passive"))
      (node (ref "R174") (pin "2") (pinfunction "2_2") (pintype "passive"))
      (node (ref "TP26") (pin "TP") (pinfunction "TP_TP") (pintype "input"))
    )
    (net (code "47") (name "LIGHT_I26") (class "Default")
      (node (ref "IC2") (pin "21") (pinfunction "I10_21") (pintype "bidirectional"))
      (node (ref "Q43") (pin "C") (pinfunction "C_C") (pintype "passive"))
      (node (ref "R175") (pin "2") (pinfunction "2_2") (pintype "passive"))
      (node (ref "TP27") (pin "TP") (pinfunction "TP_TP") (pintype "input"))
    )
    (net (code "48") (name "LIGHT_I27") (class "Default")
      (node (ref "IC2") (pin "20") (pinfunction "I11_20") (pintype "bidirectional"))
      (node (ref "Q44") (pin "C") (pinfunction "C_C") (pintype "passive"))
      (node (ref "R176") (pin "2") (pinfunction "2_2") (pintype "passive"))
      (node (ref "TP28") (pin "TP") (pinfunction "TP_TP") (pintype "input"))
    )
    (net (code "49") (name "LIGHT_I28") (class "Default")
      (node (ref "IC2") (pin "19") (pinfunction "I12_19") (pintype "bidirectional"))
      (node (ref "Q45") (pin "C") (pinfunction "C_C") (pintype "passive"))
      (node (ref "R177") (pin "2") (pinfunction "2_2") (pintype "passive"))
      (node (ref "TP29") (pin "TP") (pinfunction "TP_TP") (pintype "input"))
    )
    (net (code "50") (name "LIGHT_I29") (class "Default")
      (node (ref "IC2") (pin "18") (pinfunction "I13_18") (pintype "bidirectional"))
      (node (ref "Q46") (pin "C") (pinfunction "C_C") (pintype "passive"))
      (node (ref "R178") (pin "2") (pinfunction "2_2") (pintype "passive"))
      (node (ref "TP30") (pin "TP") (pinfunction "TP_TP") (pintype "input"))
    )
    (net (code "51") (name "LIGHT_I30") (class "Default")
      (node (ref "IC2") (pin "17") (pinfunction "I14_17") (pintype "bidirectional"))
      (node (ref "Q47") (pin "C") (pinfunction "C_C") (pintype "passive"))
      (node (ref "R179") (pin "2") (pinfunction "2_2") (pintype "passive"))
      (node (ref "TP31") (pin "TP") (pinfunction "TP_TP") (pintype "input"))
    )
    (net (code "52") (name "LIGHT_I31") (class "Default")
      (node (ref "IC2") (pin "16") (pinfunction "I15_16") (pintype "bidirectional"))
      (node (ref "Q48") (pin "C") (pinfunction "C_C") (pintype "passive"))
      (node (ref "R180") (pin "2") (pinfunction "2_2") (pintype "passive"))
      (node (ref "TP32") (pin "TP") (pinfunction "TP_TP") (pintype "input"))
    )
    (net (code "53") (name "LIGHT_READ_A") (class "Default")
      (node (ref "IC1") (pin "1") (pinfunction "COMMON_INPUT/OUTPUT_1") (pintype "bidirectional"))
      (node (ref "J1") (pin "04") (pinfunction "04_04") (pintype "passive"))
    )
    (net (code "54") (name "LIGHT_READ_B") (class "Default")
      (node (ref "IC2") (pin "1") (pinfunction "COMMON_INPUT/OUTPUT_1") (pintype "bidirectional"))
      (node (ref "J1") (pin "06") (pinfunction "06_06") (pintype "passive"))
    )
    (net (code "55") (name "LIGHT_SET_0") (class "Default")
      (node (ref "IC1") (pin "10") (pinfunction "S0_10") (pintype "bidirectional"))
      (node (ref "IC2") (pin "10") (pinfunction "S0_10") (pintype "bidirectional"))
      (node (ref "J1") (pin "35") (pinfunction "35_35") (pintype "passive"))
    )
    (net (code "56") (name "LIGHT_SET_1") (class "Default")
      (node (ref "IC1") (pin "11") (pinfunction "S1_11") (pintype "bidirectional"))
      (node (ref "IC2") (pin "11") (pinfunction "S1_11") (pintype "bidirectional"))
      (node (ref "J1") (pin "37") (pinfunction "37_37") (pintype "passive"))
    )
    (net (code "57") (name "LIGHT_SET_2") (class "Default")
      (node (ref "IC1") (pin "14") (pinfunction "S2_14") (pintype "bidirectional"))
      (node (ref "IC2") (pin "14") (pinfunction "S2_14") (pintype "bidirectional"))
      (node (ref "J1") (pin "39") (pinfunction "39_39") (pintype "passive"))
    )
    (net (code "58") (name "LIGHT_SET_3") (class "Default")
      (node (ref "IC1") (pin "13") (pinfunction "S3_13") (pintype "bidirectional"))
      (node (ref "IC2") (pin "13") (pinfunction "S3_13") (pintype "bidirectional"))
      (node (ref "J1") (pin "02") (pinfunction "02_02") (pintype "passive"))
    )
    (net (code "59") (name "Net-(D2-PadA)") (class "Default")
      (node (ref "D2") (pin "A") (pinfunction "A_A") (pintype "passive"))
      (node (ref "R117") (pin "1") (pinfunction "1_1") (pintype "passive"))
    )
    (net (code "60") (name "Net-(D3-PadA)") (class "Default")
      (node (ref "D3") (pin "A") (pinfunction "A_A") (pintype "passive"))
      (node (ref "R119") (pin "1") (pinfunction "1_1") (pintype "passive"))
    )
    (net (code "61") (name "Net-(D4-PadA)") (class "Default")
      (node (ref "D4") (pin "A") (pinfunction "A_A") (pintype "passive"))
      (node (ref "R120") (pin "1") (pinfunction "1_1") (pintype "passive"))
    )
    (net (code "62") (name "Net-(D5-PadA)") (class "Default")
      (node (ref "D5") (pin "A") (pinfunction "A_A") (pintype "passive"))
      (node (ref "R121") (pin "1") (pinfunction "1_1") (pintype "passive"))
    )
    (net (code "63") (name "Net-(D6-PadA)") (class "Default")
      (node (ref "D6") (pin "A") (pinfunction "A_A") (pintype "passive"))
      (node (ref "R122") (pin "1") (pinfunction "1_1") (pintype "passive"))
    )
    (net (code "64") (name "Net-(D7-PadA)") (class "Default")
      (node (ref "D7") (pin "A") (pinfunction "A_A") (pintype "passive"))
      (node (ref "R123") (pin "1") (pinfunction "1_1") (pintype "passive"))
    )
    (net (code "65") (name "Net-(D8-PadA)") (class "Default")
      (node (ref "D8") (pin "A") (pinfunction "A_A") (pintype "passive"))
      (node (ref "R124") (pin "1") (pinfunction "1_1") (pintype "passive"))
    )
    (net (code "66") (name "Net-(D9-PadA)") (class "Default")
      (node (ref "D9") (pin "A") (pinfunction "A_A") (pintype "passive"))
      (node (ref "R125") (pin "1") (pinfunction "1_1") (pintype "passive"))
    )
    (net (code "67") (name "Net-(D10-PadA)") (class "Default")
      (node (ref "D10") (pin "A") (pinfunction "A_A") (pintype "passive"))
      (node (ref "R126") (pin "1") (pinfunction "1_1") (pintype "passive"))
    )
    (net (code "68") (name "Net-(D11-PadA)") (class "Default")
      (node (ref "D11") (pin "A") (pinfunction "A_A") (pintype "passive"))
      (node (ref "R127") (pin "1") (pinfunction "1_1") (pintype "passive"))
    )
    (net (code "69") (name "Net-(D12-PadA)") (class "Default")
      (node (ref "D12") (pin "A") (pinfunction "A_A") (pintype "passive"))
      (node (ref "R128") (pin "1") (pinfunction "1_1") (pintype "passive"))
    )
    (net (code "70") (name "Net-(D13-PadA)") (class "Default")
      (node (ref "D13") (pin "A") (pinfunction "A_A") (pintype "passive"))
      (node (ref "R129") (pin "1") (pinfunction "1_1") (pintype "passive"))
    )
    (net (code "71") (name "Net-(D14-PadA)") (class "Default")
      (node (ref "D14") (pin "A") (pinfunction "A_A") (pintype "passive"))
      (node (ref "R130") (pin "1") (pinfunction "1_1") (pintype "passive"))
    )
    (net (code "72") (name "Net-(D15-PadA)") (class "Default")
      (node (ref "D15") (pin "A") (pinfunction "A_A") (pintype "passive"))
      (node (ref "R131") (pin "1") (pinfunction "1_1") (pintype "passive"))
    )
    (net (code "73") (name "Net-(D16-PadA)") (class "Default")
      (node (ref "D16") (pin "A") (pinfunction "A_A") (pintype "passive"))
      (node (ref "R132") (pin "1") (pinfunction "1_1") (pintype "passive"))
    )
    (net (code "74") (name "Net-(D17-PadA)") (class "Default")
      (node (ref "D17") (pin "A") (pinfunction "A_A") (pintype "passive"))
      (node (ref "R133") (pin "1") (pinfunction "1_1") (pintype "passive"))
    )
    (net (code "75") (name "Net-(D18-PadA)") (class "Default")
      (node (ref "D18") (pin "A") (pinfunction "A_A") (pintype "passive"))
      (node (ref "R134") (pin "1") (pinfunction "1_1") (pintype "passive"))
    )
    (net (code "76") (name "Net-(D19-PadA)") (class "Default")
      (node (ref "D19") (pin "A") (pinfunction "A_A") (pintype "passive"))
      (node (ref "R135") (pin "1") (pinfunction "1_1") (pintype "passive"))
    )
    (net (code "77") (name "Net-(D20-PadA)") (class "Default")
      (node (ref "D20") (pin "A") (pinfunction "A_A") (pintype "passive"))
      (node (ref "R136") (pin "1") (pinfunction "1_1") (pintype "passive"))
    )
    (net (code "78") (name "Net-(D21-PadA)") (class "Default")
      (node (ref "D21") (pin "A") (pinfunction "A_A") (pintype "passive"))
      (node (ref "R137") (pin "1") (pinfunction "1_1") (pintype "passive"))
    )
    (net (code "79") (name "Net-(D22-PadA)") (class "Default")
      (node (ref "D22") (pin "A") (pinfunction "A_A") (pintype "passive"))
      (node (ref "R138") (pin "1") (pinfunction "1_1") (pintype "passive"))
    )
    (net (code "80") (name "Net-(D23-PadA)") (class "Default")
      (node (ref "D23") (pin "A") (pinfunction "A_A") (pintype "passive"))
      (node (ref "R139") (pin "1") (pinfunction "1_1") (pintype "passive"))
    )
    (net (code "81") (name "Net-(D24-PadA)") (class "Default")
      (node (ref "D24") (pin "A") (pinfunction "A_A") (pintype "passive"))
      (node (ref "R140") (pin "1") (pinfunction "1_1") (pintype "passive"))
    )
    (net (code "82") (name "Net-(D25-PadA)") (class "Default")
      (node (ref "D25") (pin "A") (pinfunction "A_A") (pintype "passive"))
      (node (ref "R141") (pin "1") (pinfunction "1_1") (pintype "passive"))
    )
    (net (code "83") (name "Net-(D26-PadA)") (class "Default")
      (node (ref "D26") (pin "A") (pinfunction "A_A") (pintype "passive"))
      (node (ref "R142") (pin "1") (pinfunction "1_1") (pintype "passive"))
    )
    (net (code "84") (name "Net-(D27-PadA)") (class "Default")
      (node (ref "D27") (pin "A") (pinfunction "A_A") (pintype "passive"))
      (node (ref "R143") (pin "1") (pinfunction "1_1") (pintype "passive"))
    )
    (net (code "85") (name "Net-(D28-PadA)") (class "Default")
      (node (ref "D28") (pin "A") (pinfunction "A_A") (pintype "passive"))
      (node (ref "R144") (pin "1") (pinfunction "1_1") (pintype "passive"))
    )
    (net (code "86") (name "Net-(D29-PadA)") (class "Default")
      (node (ref "D29") (pin "A") (pinfunction "A_A") (pintype "passive"))
      (node (ref "R145") (pin "1") (pinfunction "1_1") (pintype "passive"))
    )
    (net (code "87") (name "Net-(D30-PadA)") (class "Default")
      (node (ref "D30") (pin "A") (pinfunction "A_A") (pintype "passive"))
      (node (ref "R146") (pin "1") (pinfunction "1_1") (pintype "passive"))
    )
    (net (code "88") (name "Net-(D31-PadA)") (class "Default")
      (node (ref "D31") (pin "A") (pinfunction "A_A") (pintype "passive"))
      (node (ref "R147") (pin "1") (pinfunction "1_1") (pintype "passive"))
    )
    (net (code "89") (name "Net-(D32-PadA)") (class "Default")
      (node (ref "D32") (pin "A") (pinfunction "A_A") (pintype "passive"))
      (node (ref "R148") (pin "1") (pinfunction "1_1") (pintype "passive"))
    )
    (net (code "90") (name "Net-(D33-PadA)") (class "Default")
      (node (ref "D33") (pin "A") (pinfunction "A_A") (pintype "passive"))
      (node (ref "R149") (pin "1") (pinfunction "1_1") (pintype "passive"))
    )
    (net (code "91") (name "Net-(D34-K)") (class "Default")
      (node (ref "D34") (pin "1") (pinfunction "K_1") (pintype "bidirectional"))
      (node (ref "L2") (pin "1") (pinfunction "1_1") (pintype "bidirectional"))
      (node (ref "U8") (pin "3") (pinfunction "SW_3") (pintype "output"))
      (node (ref "U8") (pin "3.1") (pinfunction "SW_3.1") (pintype "output"))
    )
    (net (code "92") (name "Net-(D35-K)") (class "Default")
      (node (ref "D35") (pin "1") (pinfunction "K_1") (pintype "bidirectional"))
      (node (ref "L3") (pin "1") (pinfunction "1_1") (pintype "bidirectional"))
      (node (ref "U9") (pin "3") (pinfunction "SW_3") (pintype "output"))
      (node (ref "U9") (pin "3.1") (pinfunction "SW_3.1") (pintype "output"))
    )
    (net (code "93") (name "Net-(MOTOR_A_DRV-EN_A{slash}DIAG_A)") (class "Default")
      (node (ref "MOTOR_A_DRV") (pin "P$10") (pinfunction "EN_B/DIAG_B_P$10") (pintype "bidirectional"))
      (node (ref "MOTOR_A_DRV") (pin "P$6") (pinfunction "EN_A/DIAG_A_P$6") (pintype "bidirectional"))
      (node (ref "Q9") (pin "3") (pinfunction "D_3") (pintype "passive"))
      (node (ref "R95") (pin "1") (pinfunction "1_1") (pintype "passive"))
      (node (ref "R96") (pin "1") (pinfunction "1_1") (pintype "passive"))
    )
    (net (code "94") (name "Net-(MOTOR_A_DRV-IN_A)") (class "Default")
      (node (ref "MOTOR_A_DRV") (pin "P$5") (pinfunction "IN_A_P$5") (pintype "input"))
      (node (ref "R91") (pin "2") (pinfunction "2_2") (pintype "passive"))
    )
    (net (code "95") (name "Net-(MOTOR_A_DRV-IN_B)") (class "Default")
      (node (ref "MOTOR_A_DRV") (pin "P$11") (pinfunction "IN_B_P$11") (pintype "input"))
      (node (ref "R92") (pin "2") (pinfunction "2_2") (pintype "passive"))
    )
    (net (code "96") (name "Net-(MOTOR_A_DRV-PWM)") (class "Default")
      (node (ref "MOTOR_A_DRV") (pin "P$8") (pinfunction "PWM_P$8") (pintype "input"))
      (node (ref "R93") (pin "1") (pinfunction "1_1") (pintype "passive"))
    )
    (net (code "97") (name "Net-(MOTOR_B_DRV-EN_A{slash}DIAG_A)") (class "Default")
      (node (ref "MOTOR_B_DRV") (pin "P$10") (pinfunction "EN_B/DIAG_B_P$10") (pintype "bidirectional"))
      (node (ref "MOTOR_B_DRV") (pin "P$6") (pinfunction "EN_A/DIAG_A_P$6") (pintype "bidirectional"))
      (node (ref "Q1") (pin "3") (pinfunction "D_3") (pintype "passive"))
      (node (ref "R65") (pin "1") (pinfunction "1_1") (pintype "passive"))
      (node (ref "R74") (pin "1") (pinfunction "1_1") (pintype "passive"))
    )
    (net (code "98") (name "Net-(MOTOR_B_DRV-IN_A)") (class "Default")
      (node (ref "MOTOR_B_DRV") (pin "P$5") (pinfunction "IN_A_P$5") (pintype "input"))
      (node (ref "R70") (pin "2") (pinfunction "2_2") (pintype "passive"))
    )
    (net (code "99") (name "Net-(MOTOR_B_DRV-IN_B)") (class "Default")
      (node (ref "MOTOR_B_DRV") (pin "P$11") (pinfunction "IN_B_P$11") (pintype "input"))
      (node (ref "R71") (pin "2") (pinfunction "2_2") (pintype "passive"))
    )
    (net (code "100") (name "Net-(MOTOR_B_DRV-PWM)") (class "Default")
      (node (ref "MOTOR_B_DRV") (pin "P$8") (pinfunction "PWM_P$8") (pintype "input"))
      (node (ref "R72") (pin "1") (pinfunction "1_1") (pintype "passive"))
    )
    (net (code "101") (name "Net-(MOTOR_CON_A-NEG)") (class "Default")
      (node (ref "MOTOR_A_DRV") (pin "P$15") (pinfunction "OUT_B_P$15") (pintype "output"))
      (node (ref "MOTOR_A_DRV") (pin "P$16") (pinfunction "OUT_B_P$16") (pintype "output"))
      (node (ref "MOTOR_A_DRV") (pin "P$21") (pinfunction "OUT_B_P$21") (pintype "output"))
      (node (ref "MOTOR_CON_A") (pin "N") (pinfunction "NEG_N") (pintype "passive"))
    )
    (net (code "102") (name "Net-(MOTOR_CON_A-POS)") (class "Default")
      (node (ref "MOTOR_A_DRV") (pin "P$1") (pinfunction "OUT_A_P$1") (pintype "output"))
      (node (ref "MOTOR_A_DRV") (pin "P$25") (pinfunction "OUT_A_P$25") (pintype "output"))
      (node (ref "MOTOR_A_DRV") (pin "P$30") (pinfunction "OUT_A_P$30") (pintype "output"))
      (node (ref "MOTOR_CON_A") (pin "P") (pinfunction "POS_P") (pintype "passive"))
    )
    (net (code "103") (name "Net-(MOTOR_CON_B-NEG)") (class "Default")
      (node (ref "MOTOR_B_DRV") (pin "P$15") (pinfunction "OUT_B_P$15") (pintype "output"))
      (node (ref "MOTOR_B_DRV") (pin "P$16") (pinfunction "OUT_B_P$16") (pintype "output"))
      (node (ref "MOTOR_B_DRV") (pin "P$21") (pinfunction "OUT_B_P$21") (pintype "output"))
      (node (ref "MOTOR_CON_B") (pin "N") (pinfunction "NEG_N") (pintype "passive"))
    )
    (net (code "104") (name "Net-(MOTOR_CON_B-POS)") (class "Default")
      (node (ref "MOTOR_B_DRV") (pin "P$1") (pinfunction "OUT_A_P$1") (pintype "output"))
      (node (ref "MOTOR_B_DRV") (pin "P$25") (pinfunction "OUT_A_P$25") (pintype "output"))
      (node (ref "MOTOR_B_DRV") (pin "P$30") (pinfunction "OUT_A_P$30") (pintype "output"))
      (node (ref "MOTOR_CON_B") (pin "P") (pinfunction "POS_P") (pintype "passive"))
    )
    (net (code "105") (name "Net-(MOTOR_CON_C-NEG)") (class "Default")
      (node (ref "MOTOR_CON_C") (pin "N") (pinfunction "NEG_N") (pintype "passive"))
      (node (ref "MOTOR_C_DRV") (pin "P$15") (pinfunction "OUT_B_P$15") (pintype "output"))
      (node (ref "MOTOR_C_DRV") (pin "P$16") (pinfunction "OUT_B_P$16") (pintype "output"))
      (node (ref "MOTOR_C_DRV") (pin "P$21") (pinfunction "OUT_B_P$21") (pintype "output"))
    )
    (net (code "106") (name "Net-(MOTOR_CON_C-POS)") (class "Default")
      (node (ref "MOTOR_CON_C") (pin "P") (pinfunction "POS_P") (pintype "passive"))
      (node (ref "MOTOR_C_DRV") (pin "P$1") (pinfunction "OUT_A_P$1") (pintype "output"))
      (node (ref "MOTOR_C_DRV") (pin "P$25") (pinfunction "OUT_A_P$25") (pintype "output"))
      (node (ref "MOTOR_C_DRV") (pin "P$30") (pinfunction "OUT_A_P$30") (pintype "output"))
    )
    (net (code "107") (name "Net-(MOTOR_CON_D-NEG)") (class "Default")
      (node (ref "MOTOR_CON_D") (pin "N") (pinfunction "NEG_N") (pintype "passive"))
      (node (ref "MOTOR_D_DRV") (pin "P$15") (pinfunction "OUT_B_P$15") (pintype "output"))
      (node (ref "MOTOR_D_DRV") (pin "P$16") (pinfunction "OUT_B_P$16") (pintype "output"))
      (node (ref "MOTOR_D_DRV") (pin "P$21") (pinfunction "OUT_B_P$21") (pintype "output"))
    )
    (net (code "108") (name "Net-(MOTOR_CON_D-POS)") (class "Default")
      (node (ref "MOTOR_CON_D") (pin "P") (pinfunction "POS_P") (pintype "passive"))
      (node (ref "MOTOR_D_DRV") (pin "P$1") (pinfunction "OUT_A_P$1") (pintype "output"))
      (node (ref "MOTOR_D_DRV") (pin "P$25") (pinfunction "OUT_A_P$25") (pintype "output"))
      (node (ref "MOTOR_D_DRV") (pin "P$30") (pinfunction "OUT_A_P$30") (pintype "output"))
    )
    (net (code "109") (name "Net-(MOTOR_C_DRV-EN_A{slash}DIAG_A)") (class "Default")
      (node (ref "MOTOR_C_DRV") (pin "P$10") (pinfunction "EN_B/DIAG_B_P$10") (pintype "bidirectional"))
      (node (ref "MOTOR_C_DRV") (pin "P$6") (pinfunction "EN_A/DIAG_A_P$6") (pintype "bidirectional"))
      (node (ref "Q13") (pin "3") (pinfunction "D_3") (pintype "passive"))
      (node (ref "R108") (pin "1") (pinfunction "1_1") (pintype "passive"))
      (node (ref "R109") (pin "1") (pinfunction "1_1") (pintype "passive"))
    )
    (net (code "110") (name "Net-(MOTOR_C_DRV-IN_A)") (class "Default")
      (node (ref "MOTOR_C_DRV") (pin "P$5") (pinfunction "IN_A_P$5") (pintype "input"))
      (node (ref "R104") (pin "2") (pinfunction "2_2") (pintype "passive"))
    )
    (net (code "111") (name "Net-(MOTOR_C_DRV-IN_B)") (class "Default")
      (node (ref "MOTOR_C_DRV") (pin "P$11") (pinfunction "IN_B_P$11") (pintype "input"))
      (node (ref "R105") (pin "2") (pinfunction "2_2") (pintype "passive"))
    )
    (net (code "112") (name "Net-(MOTOR_C_DRV-PWM)") (class "Default")
      (node (ref "MOTOR_C_DRV") (pin "P$8") (pinfunction "PWM_P$8") (pintype "input"))
      (node (ref "R106") (pin "1") (pinfunction "1_1") (pintype "passive"))
    )
    (net (code "113") (name "Net-(MOTOR_D_DRV-EN_A{slash}DIAG_A)") (class "Default")
      (node (ref "MOTOR_D_DRV") (pin "P$10") (pinfunction "EN_B/DIAG_B_P$10") (pintype "bidirectional"))
      (node (ref "MOTOR_D_DRV") (pin "P$6") (pinfunction "EN_A/DIAG_A_P$6") (pintype "bidirectional"))
      (node (ref "Q5") (pin "3") (pinfunction "D_3") (pintype "passive"))
      (node (ref "R82") (pin "1") (pinfunction "1_1") (pintype "passive"))
      (node (ref "R83") (pin "1") (pinfunction "1_1") (pintype "passive"))
    )
    (net (code "114") (name "Net-(MOTOR_D_DRV-IN_A)") (class "Default")
      (node (ref "MOTOR_D_DRV") (pin "P$5") (pinfunction "IN_A_P$5") (pintype "input"))
      (node (ref "R78") (pin "2") (pinfunction "2_2") (pintype "passive"))
    )
    (net (code "115") (name "Net-(MOTOR_D_DRV-IN_B)") (class "Default")
      (node (ref "MOTOR_D_DRV") (pin "P$11") (pinfunction "IN_B_P$11") (pintype "input"))
      (node (ref "R79") (pin "2") (pinfunction "2_2") (pintype "passive"))
    )
    (net (code "116") (name "Net-(MOTOR_D_DRV-PWM)") (class "Default")
      (node (ref "MOTOR_D_DRV") (pin "P$8") (pinfunction "PWM_P$8") (pintype "input"))
      (node (ref "R80") (pin "1") (pinfunction "1_1") (pintype "passive"))
    )
    (net (code "117") (name "Net-(Q2-D)") (class "Default")
      (node (ref "Q2") (pin "3") (pinfunction "D_3") (pintype "passive"))
      (node (ref "R70") (pin "1") (pinfunction "1_1") (pintype "passive"))
      (node (ref "R75") (pin "1") (pinfunction "1_1") (pintype "passive"))
    )
    (net (code "118") (name "Net-(Q3-D)") (class "Default")
      (node (ref "Q3") (pin "3") (pinfunction "D_3") (pintype "passive"))
      (node (ref "R71") (pin "1") (pinfunction "1_1") (pintype "passive"))
      (node (ref "R76") (pin "1") (pinfunction "1_1") (pintype "passive"))
    )
    (net (code "119") (name "Net-(Q4-D)") (class "Default")
      (node (ref "Q4") (pin "3") (pinfunction "D_3") (pintype "passive"))
      (node (ref "R72") (pin "2") (pinfunction "2_2") (pintype "passive"))
      (node (ref "R73") (pin "1") (pinfunction "1_1") (pintype "passive"))
      (node (ref "R77") (pin "1") (pinfunction "1_1") (pintype "passive"))
    )
    (net (code "120") (name "Net-(Q6-D)") (class "Default")
      (node (ref "Q6") (pin "3") (pinfunction "D_3") (pintype "passive"))
      (node (ref "R78") (pin "1") (pinfunction "1_1") (pintype "passive"))
      (node (ref "R88") (pin "1") (pinfunction "1_1") (pintype "passive"))
    )
    (net (code "121") (name "Net-(Q7-D)") (class "Default")
      (node (ref "Q7") (pin "3") (pinfunction "D_3") (pintype "passive"))
      (node (ref "R79") (pin "1") (pinfunction "1_1") (pintype "passive"))
      (node (ref "R89") (pin "1") (pinfunction "1_1") (pintype "passive"))
    )
    (net (code "122") (name "Net-(Q8-D)") (class "Default")
      (node (ref "Q8") (pin "3") (pinfunction "D_3") (pintype "passive"))
      (node (ref "R80") (pin "2") (pinfunction "2_2") (pintype "passive"))
      (node (ref "R81") (pin "1") (pinfunction "1_1") (pintype "passive"))
      (node (ref "R90") (pin "1") (pinfunction "1_1") (pintype "passive"))
    )
    (net (code "123") (name "Net-(Q10-D)") (class "Default")
      (node (ref "Q10") (pin "3") (pinfunction "D_3") (pintype "passive"))
      (node (ref "R101") (pin "1") (pinfunction "1_1") (pintype "passive"))
      (node (ref "R91") (pin "1") (pinfunction "1_1") (pintype "passive"))
    )
    (net (code "124") (name "Net-(Q11-D)") (class "Default")
      (node (ref "Q11") (pin "3") (pinfunction "D_3") (pintype "passive"))
      (node (ref "R102") (pin "1") (pinfunction "1_1") (pintype "passive"))
      (node (ref "R92") (pin "1") (pinfunction "1_1") (pintype "passive"))
    )
    (net (code "125") (name "Net-(Q12-D)") (class "Default")
      (node (ref "Q12") (pin "3") (pinfunction "D_3") (pintype "passive"))
      (node (ref "R103") (pin "1") (pinfunction "1_1") (pintype "passive"))
      (node (ref "R93") (pin "2") (pinfunction "2_2") (pintype "passive"))
      (node (ref "R94") (pin "1") (pinfunction "1_1") (pintype "passive"))
    )
    (net (code "126") (name "Net-(Q14-D)") (class "Default")
      (node (ref "Q14") (pin "3") (pinfunction "D_3") (pintype "passive"))
      (node (ref "R104") (pin "1") (pinfunction "1_1") (pintype "passive"))
      (node (ref "R114") (pin "1") (pinfunction "1_1") (pintype "passive"))
    )
    (net (code "127") (name "Net-(Q15-D)") (class "Default")
      (node (ref "Q15") (pin "3") (pinfunction "D_3") (pintype "passive"))
      (node (ref "R105") (pin "1") (pinfunction "1_1") (pintype "passive"))
      (node (ref "R115") (pin "1") (pinfunction "1_1") (pintype "passive"))
    )
    (net (code "128") (name "Net-(Q16-D)") (class "Default")
      (node (ref "Q16") (pin "3") (pinfunction "D_3") (pintype "passive"))
      (node (ref "R106") (pin "2") (pinfunction "2_2") (pintype "passive"))
      (node (ref "R107") (pin "1") (pinfunction "1_1") (pintype "passive"))
      (node (ref "R116") (pin "1") (pinfunction "1_1") (pintype "passive"))
    )
    (net (code "129") (name "Net-(Q49-D)") (class "Default")
      (node (ref "C10") (pin "1") (pinfunction "1_1") (pintype "passive"))
      (node (ref "C13") (pin "1") (pinfunction "1_1") (pintype "passive"))
      (node (ref "C14") (pin "1") (pinfunction "1_1") (pintype "passive"))
      (node (ref "C17") (pin "1") (pinfunction "1_1") (pintype "passive"))
      (node (ref "C18") (pin "1") (pinfunction "1_1") (pintype "passive"))
      (node (ref "C21") (pin "1") (pinfunction "1_1") (pintype "passive"))
      (node (ref "C22") (pin "1") (pinfunction "1_1") (pintype "passive"))
      (node (ref "C25") (pin "1") (pinfunction "1_1") (pintype "passive"))
      (node (ref "C26") (pin "1") (pinfunction "1_1") (pintype "passive"))
      (node (ref "C29") (pin "1") (pinfunction "1_1") (pintype "passive"))
      (node (ref "C30") (pin "1") (pinfunction "1_1") (pintype "passive"))
      (node (ref "C33") (pin "1") (pinfunction "1_1") (pintype "passive"))
      (node (ref "C34") (pin "1") (pinfunction "1_1") (pintype "passive"))
      (node (ref "C37") (pin "1") (pinfunction "1_1") (pintype "passive"))
      (node (ref "C38") (pin "1") (pinfunction "1_1") (pintype "passive"))
      (node (ref "C9") (pin "1") (pinfunction "1_1") (pintype "passive"))
      (node (ref "D10") (pin "C") (pinfunction "C_C") (pintype "passive"))
      (node (ref "D11") (pin "C") (pinfunction "C_C") (pintype "passive"))
      (node (ref "D12") (pin "C") (pinfunction "C_C") (pintype "passive"))
      (node (ref "D13") (pin "C") (pinfunction "C_C") (pintype "passive"))
      (node (ref "D14") (pin "C") (pinfunction "C_C") (pintype "passive"))
      (node (ref "D15") (pin "C") (pinfunction "C_C") (pintype "passive"))
      (node (ref "D16") (pin "C") (pinfunction "C_C") (pintype "passive"))
      (node (ref "D17") (pin "C") (pinfunction "C_C") (pintype "passive"))
      (node (ref "D2") (pin "C") (pinfunction "C_C") (pintype "passive"))
      (node (ref "D3") (pin "C") (pinfunction "C_C") (pintype "passive"))
      (node (ref "D4") (pin "C") (pinfunction "C_C") (pintype "passive"))
      (node (ref "D5") (pin "C") (pinfunction "C_C") (pintype "passive"))
      (node (ref "D6") (pin "C") (pinfunction "C_C") (pintype "passive"))
      (node (ref "D7") (pin "C") (pinfunction "C_C") (pintype "passive"))
      (node (ref "D8") (pin "C") (pinfunction "C_C") (pintype "passive"))
      (node (ref "D9") (pin "C") (pinfunction "C_C") (pintype "passive"))
      (node (ref "Q49") (pin "2") (pinfunction "D_2") (pintype "passive"))
    )
    (net (code "130") (name "Net-(Q49-G)") (class "Default")
      (node (ref "Q49") (pin "1") (pinfunction "G_1") (pintype "passive"))
      (node (ref "Q52") (pin "3") (pinfunction "D_3") (pintype "passive"))
      (node (ref "R5") (pin "1") (pinfunction "1_1") (pintype "passive"))
    )
    (net (code "131") (name "Net-(Q50-D)") (class "Default")
      (node (ref "Q50") (pin "2") (pinfunction "D_2") (pintype "passive"))
      (node (ref "SOLENOID_CON") (pin "N") (pinfunction "NEG_N") (pintype "passive"))
    )
    (net (code "132") (name "Net-(Q50-G)") (class "Default")
      (node (ref "Q50") (pin "1") (pinfunction "G_1") (pintype "passive"))
      (node (ref "Q51") (pin "3") (pinfunction "D_3") (pintype "passive"))
      (node (ref "R1") (pin "1") (pinfunction "1_1") (pintype "passive"))
    )
    (net (code "133") (name "Net-(Q53-D)") (class "Default")
      (node (ref "C11") (pin "1") (pinfunction "1_1") (pintype "passive"))
      (node (ref "C12") (pin "1") (pinfunction "1_1") (pintype "passive"))
      (node (ref "C15") (pin "1") (pinfunction "1_1") (pintype "passive"))
      (node (ref "C16") (pin "1") (pinfunction "1_1") (pintype "passive"))
      (node (ref "C19") (pin "1") (pinfunction "1_1") (pintype "passive"))
      (node (ref "C20") (pin "1") (pinfunction "1_1") (pintype "passive"))
      (node (ref "C23") (pin "1") (pinfunction "1_1") (pintype "passive"))
      (node (ref "C24") (pin "1") (pinfunction "1_1") (pintype "passive"))
      (node (ref "C27") (pin "1") (pinfunction "1_1") (pintype "passive"))
      (node (ref "C28") (pin "1") (pinfunction "1_1") (pintype "passive"))
      (node (ref "C31") (pin "1") (pinfunction "1_1") (pintype "passive"))
      (node (ref "C32") (pin "1") (pinfunction "1_1") (pintype "passive"))
      (node (ref "C35") (pin "1") (pinfunction "1_1") (pintype "passive"))
      (node (ref "C36") (pin "1") (pinfunction "1_1") (pintype "passive"))
      (node (ref "C39") (pin "1") (pinfunction "1_1") (pintype "passive"))
      (node (ref "C40") (pin "1") (pinfunction "1_1") (pintype "passive"))
      (node (ref "D18") (pin "C") (pinfunction "C_C") (pintype "passive"))
      (node (ref "D19") (pin "C") (pinfunction "C_C") (pintype "passive"))
      (node (ref "D20") (pin "C") (pinfunction "C_C") (pintype "passive"))
      (node (ref "D21") (pin "C") (pinfunction "C_C") (pintype "passive"))
      (node (ref "D22") (pin "C") (pinfunction "C_C") (pintype "passive"))
      (node (ref "D23") (pin "C") (pinfunction "C_C") (pintype "passive"))
      (node (ref "D24") (pin "C") (pinfunction "C_C") (pintype "passive"))
      (node (ref "D25") (pin "C") (pinfunction "C_C") (pintype "passive"))
      (node (ref "D26") (pin "C") (pinfunction "C_C") (pintype "passive"))
      (node (ref "D27") (pin "C") (pinfunction "C_C") (pintype "passive"))
      (node (ref "D28") (pin "C") (pinfunction "C_C") (pintype "passive"))
      (node (ref "D29") (pin "C") (pinfunction "C_C") (pintype "passive"))
      (node (ref "D30") (pin "C") (pinfunction "C_C") (pintype "passive"))
      (node (ref "D31") (pin "C") (pinfunction "C_C") (pintype "passive"))
      (node (ref "D32") (pin "C") (pinfunction "C_C") (pintype "passive"))
      (node (ref "D33") (pin "C") (pinfunction "C_C") (pintype "passive"))
      (node (ref "Q53") (pin "2") (pinfunction "D_2") (pintype "passive"))
    )
    (net (code "134") (name "Net-(Q53-G)") (class "Default")
      (node (ref "Q53") (pin "1") (pinfunction "G_1") (pintype "passive"))
      (node (ref "Q54") (pin "3") (pinfunction "D_3") (pintype "passive"))
      (node (ref "R7") (pin "1") (pinfunction "1_1") (pintype "passive"))
    )
    (net (code "135") (name "Net-(R3-S)") (class "Default")
      (node (ref "C50") (pin "2") (pinfunction "2_2") (pintype "passive"))
      (node (ref "R3") (pin "2") (pinfunction "S_2") (pintype "passive"))
      (node (ref "U8") (pin "2") (pinfunction "FB_2") (pintype "input"))
    )
    (net (code "136") (name "Net-(R4-S)") (class "Default")
      (node (ref "C53") (pin "2") (pinfunction "2_2") (pintype "passive"))
      (node (ref "R4") (pin "2") (pinfunction "S_2") (pintype "passive"))
      (node (ref "U9") (pin "2") (pinfunction "FB_2") (pintype "input"))
    )
    (net (code "137") (name "Net-(SWITCH_CON-POS)") (class "Default")
      (node (ref "SWITCH_CON") (pin "P") (pinfunction "POS_P") (pintype "passive"))
      (node (ref "U1") (pin "N") (pinfunction "-_N") (pintype "passive"))
    )
    (net (code "138") (name "Net-(U1-+)") (class "Default")
      (node (ref "U1") (pin "P") (pinfunction "+_P") (pintype "passive"))
      (node (ref "U3") (pin "N") (pinfunction "-_N") (pintype "passive"))
    )
    (net (code "139") (name "Net-(U2--)") (class "Default")
      (node (ref "U2") (pin "N") (pinfunction "-_N") (pintype "passive"))
      (node (ref "U3") (pin "P") (pinfunction "+_P") (pintype "passive"))
    )
    (net (code "140") (name "PWM_A") (class "Default")
      (node (ref "J1") (pin "09") (pinfunction "09_09") (pintype "passive"))
      (node (ref "Q12") (pin "2") (pinfunction "S_2") (pintype "passive"))
      (node (ref "R100") (pin "1") (pinfunction "1_1") (pintype "passive"))
    )
    (net (code "141") (name "PWM_B") (class "Default")
      (node (ref "J1") (pin "17") (pinfunction "17_17") (pintype "passive"))
      (node (ref "Q4") (pin "2") (pinfunction "S_2") (pintype "passive"))
      (node (ref "R69") (pin "1") (pinfunction "1_1") (pintype "passive"))
    )
    (net (code "142") (name "PWM_C") (class "Default")
      (node (ref "J1") (pin "25") (pinfunction "25_25") (pintype "passive"))
      (node (ref "Q16") (pin "2") (pinfunction "S_2") (pintype "passive"))
      (node (ref "R113") (pin "1") (pinfunction "1_1") (pintype "passive"))
    )
    (net (code "143") (name "PWM_D") (class "Default")
      (node (ref "J1") (pin "33") (pinfunction "33_33") (pintype "passive"))
      (node (ref "Q8") (pin "2") (pinfunction "S_2") (pintype "passive"))
      (node (ref "R87") (pin "1") (pinfunction "1_1") (pintype "passive"))
    )
    (net (code "144") (name "unconnected-(MOTOR_A_DRV-CS-PadP$9)") (class "Default")
      (node (ref "MOTOR_A_DRV") (pin "P$9") (pinfunction "CS_P$9") (pintype "output"))
    )
    (net (code "145") (name "unconnected-(MOTOR_B_DRV-CS-PadP$9)") (class "Default")
      (node (ref "MOTOR_B_DRV") (pin "P$9") (pinfunction "CS_P$9") (pintype "output"))
    )
    (net (code "146") (name "unconnected-(MOTOR_C_DRV-CS-PadP$9)") (class "Default")
      (node (ref "MOTOR_C_DRV") (pin "P$9") (pinfunction "CS_P$9") (pintype "output"))
    )
    (net (code "147") (name "unconnected-(MOTOR_D_DRV-CS-PadP$9)") (class "Default")
      (node (ref "MOTOR_D_DRV") (pin "P$9") (pinfunction "CS_P$9") (pintype "output"))
    )
  )
)
